# ARM_board.net
KiCad netlist of a schematic drawn in EAGLE
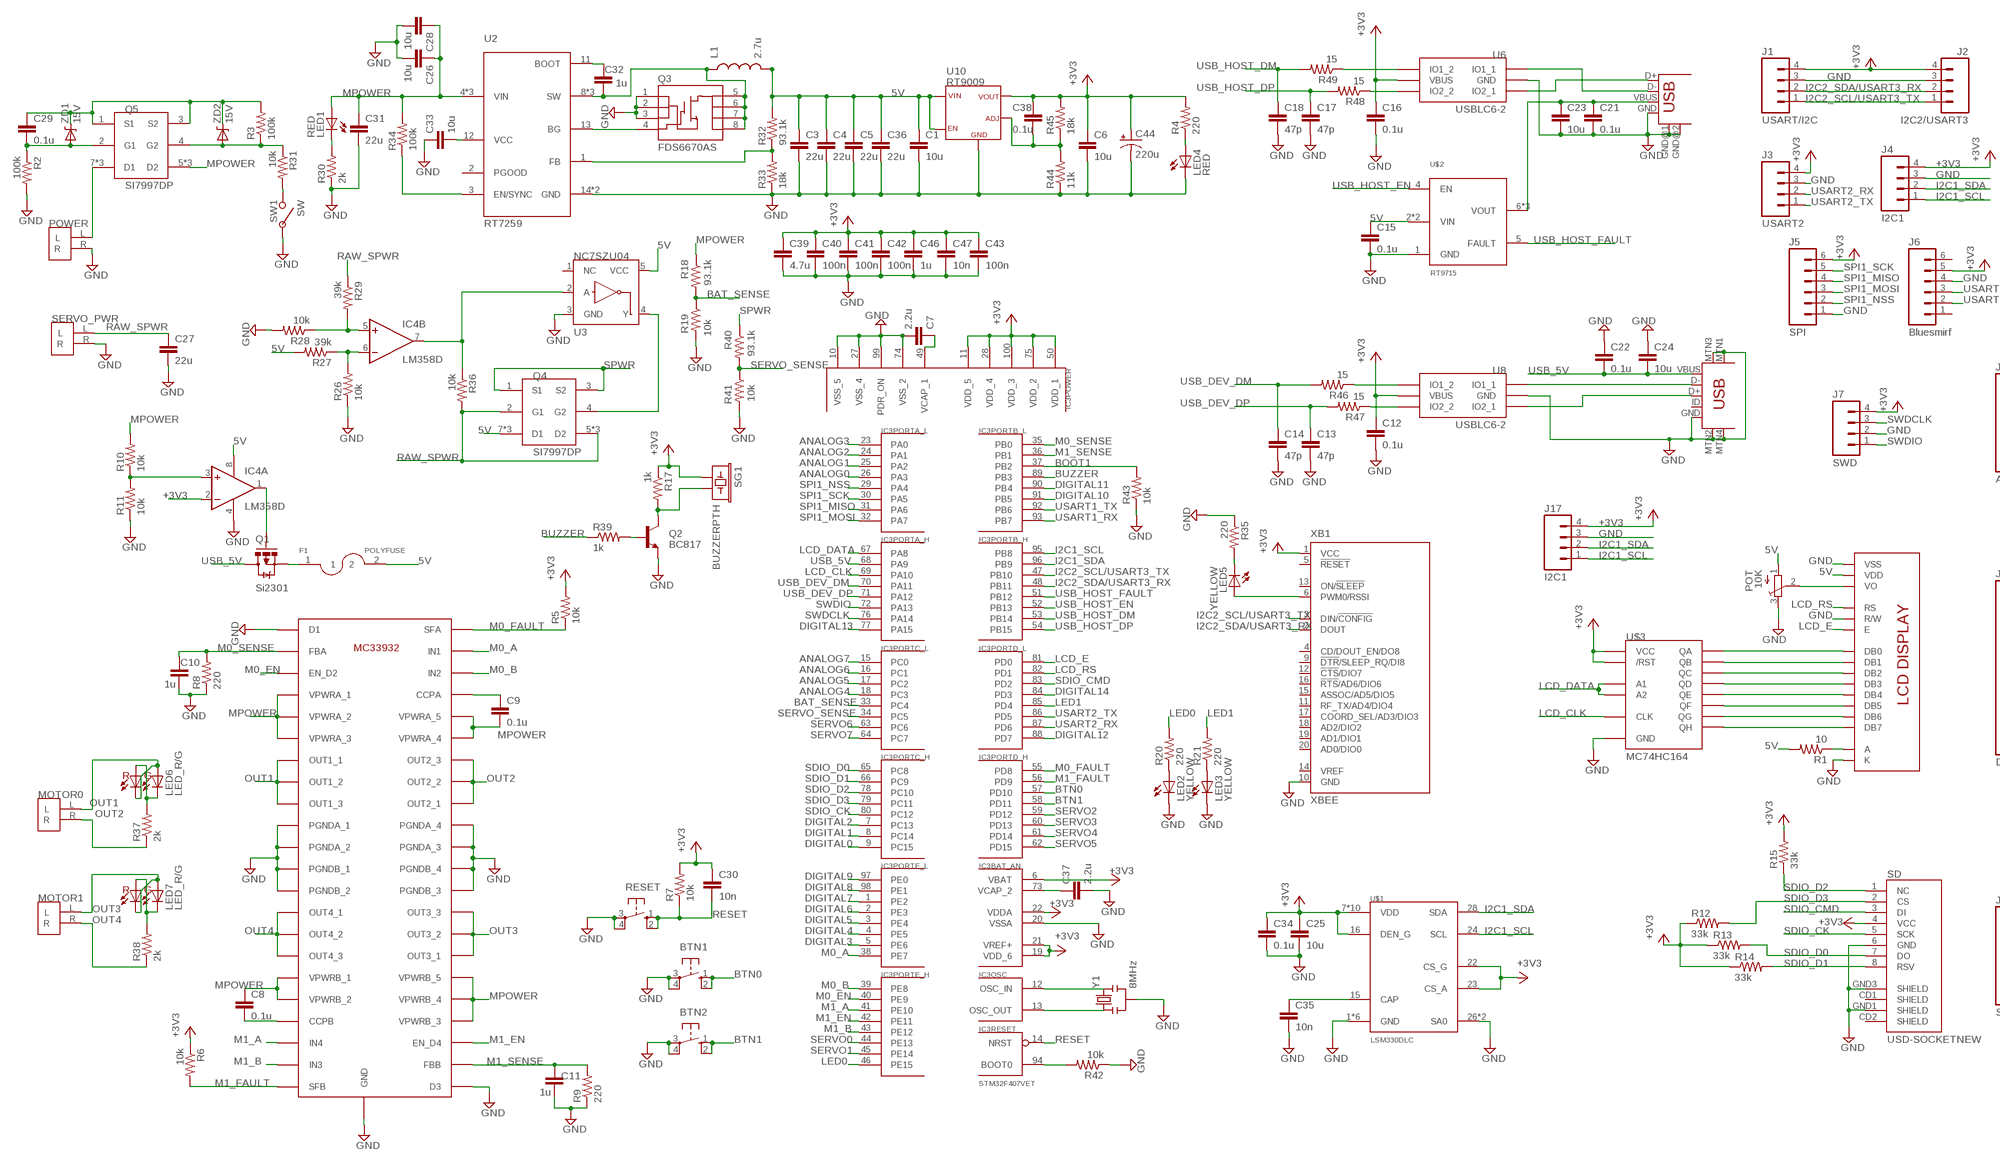
[diagram p0: schematic, sheet 1, part 1 of 2]
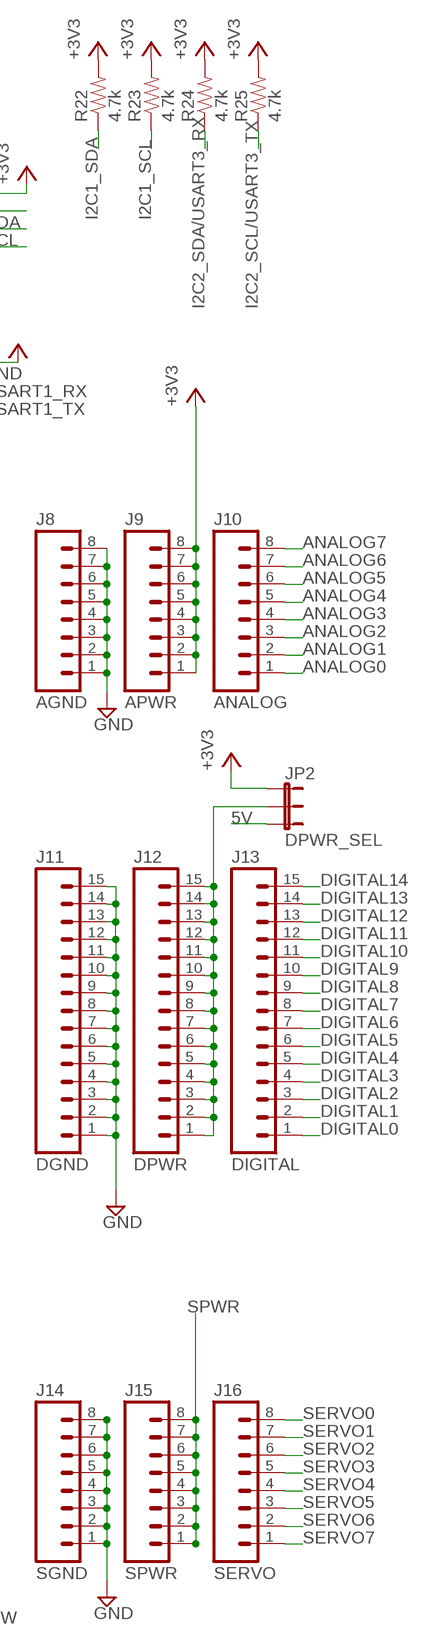
[diagram p1: schematic, sheet 1, part 2 of 2]

(export (version "E")
  (design (tool "Eeschema 10.0.6"))
  (components
    (comp (ref "BTN1")
      (value "10-XX")
      (footprint "eagle-import:B3F-10XX")
      (fields (field (name "MPN") "B3F-1000"))
      (libsource (lib "eagle-import") (part "10-XX"))
    )
    (comp (ref "BTN2")
      (value "10-XX")
      (footprint "eagle-import:B3F-10XX")
      (fields (field (name "MPN") "B3F-1000"))
      (libsource (lib "eagle-import") (part "10-XX"))
    )
    (comp (ref "C1")
      (value "10u")
      (footprint "eagle-import:0805")
      (libsource (lib "eagle-import") (part "CAP0805"))
    )
    (comp (ref "C3")
      (value "22u")
      (footprint "eagle-import:0805")
      (libsource (lib "eagle-import") (part "CAP0805"))
    )
    (comp (ref "C4")
      (value "22u")
      (footprint "eagle-import:0805")
      (libsource (lib "eagle-import") (part "CAP0805"))
    )
    (comp (ref "C5")
      (value "22u")
      (footprint "eagle-import:0805")
      (libsource (lib "eagle-import") (part "CAP0805"))
    )
    (comp (ref "C6")
      (value "10u")
      (footprint "eagle-import:0805")
      (libsource (lib "eagle-import") (part "CAP0805"))
    )
    (comp (ref "C7")
      (value "2.2u")
      (footprint "eagle-import:0603-CAP")
      (libsource (lib "eagle-import") (part "CAP0603-CAP"))
    )
    (comp (ref "C8")
      (value "0.1u")
      (footprint "eagle-import:0603-CAP")
      (libsource (lib "eagle-import") (part "CAP0603-CAP"))
    )
    (comp (ref "C9")
      (value "0.1u")
      (footprint "eagle-import:0603-CAP")
      (libsource (lib "eagle-import") (part "CAP0603-CAP"))
    )
    (comp (ref "C10")
      (value "1u")
      (footprint "eagle-import:0603-CAP")
      (libsource (lib "eagle-import") (part "CAP0603-CAP"))
    )
    (comp (ref "C11")
      (value "1u")
      (footprint "eagle-import:0603-CAP")
      (libsource (lib "eagle-import") (part "CAP0603-CAP"))
    )
    (comp (ref "C12")
      (value "0.1u")
      (footprint "eagle-import:0603-CAP")
      (libsource (lib "eagle-import") (part "CAP0603-CAP"))
    )
    (comp (ref "C13")
      (value "47p")
      (footprint "eagle-import:0603-CAP")
      (libsource (lib "eagle-import") (part "CAP0603-CAP"))
    )
    (comp (ref "C14")
      (value "47p")
      (footprint "eagle-import:0603-CAP")
      (libsource (lib "eagle-import") (part "CAP0603-CAP"))
    )
    (comp (ref "C15")
      (value "0.1u")
      (footprint "eagle-import:0603-CAP")
      (libsource (lib "eagle-import") (part "CAP0603-CAP"))
    )
    (comp (ref "C16")
      (value "0.1u")
      (footprint "eagle-import:0603-CAP")
      (libsource (lib "eagle-import") (part "CAP0603-CAP"))
    )
    (comp (ref "C17")
      (value "47p")
      (footprint "eagle-import:0603-CAP")
      (libsource (lib "eagle-import") (part "CAP0603-CAP"))
    )
    (comp (ref "C18")
      (value "47p")
      (footprint "eagle-import:0603-CAP")
      (libsource (lib "eagle-import") (part "CAP0603-CAP"))
    )
    (comp (ref "C21")
      (value "0.1u")
      (footprint "eagle-import:0603-CAP")
      (libsource (lib "eagle-import") (part "CAP0603-CAP"))
    )
    (comp (ref "C22")
      (value "0.1u")
      (footprint "eagle-import:0603-CAP")
      (libsource (lib "eagle-import") (part "CAP0603-CAP"))
    )
    (comp (ref "C23")
      (value "10u")
      (footprint "eagle-import:0805")
      (libsource (lib "eagle-import") (part "CAP0805"))
    )
    (comp (ref "C24")
      (value "10u")
      (footprint "eagle-import:0805")
      (libsource (lib "eagle-import") (part "CAP0805"))
    )
    (comp (ref "C25")
      (value "10u")
      (footprint "eagle-import:0603-CAP")
      (libsource (lib "eagle-import") (part "CAP0603-CAP"))
    )
    (comp (ref "C26")
      (value "10u")
      (footprint "eagle-import:1206")
      (libsource (lib "eagle-import") (part "CAP1206"))
    )
    (comp (ref "C27")
      (value "22u")
      (footprint "eagle-import:1206")
      (libsource (lib "eagle-import") (part "CAP1206"))
    )
    (comp (ref "C28")
      (value "10u")
      (footprint "eagle-import:1206")
      (libsource (lib "eagle-import") (part "CAP1206"))
    )
    (comp (ref "C29")
      (value "0.1u")
      (footprint "eagle-import:0603-CAP")
      (libsource (lib "eagle-import") (part "CAP0603-CAP"))
    )
    (comp (ref "C30")
      (value "10n")
      (footprint "eagle-import:0603-CAP")
      (libsource (lib "eagle-import") (part "CAP0603-CAP"))
    )
    (comp (ref "C31")
      (value "22u")
      (footprint "eagle-import:1206")
      (libsource (lib "eagle-import") (part "CAP1206"))
    )
    (comp (ref "C32")
      (value "1u")
      (footprint "eagle-import:0603-CAP")
      (libsource (lib "eagle-import") (part "CAP0603-CAP"))
    )
    (comp (ref "C33")
      (value "10u")
      (footprint "eagle-import:0805")
      (libsource (lib "eagle-import") (part "CAP0805"))
    )
    (comp (ref "C34")
      (value "0.1u")
      (footprint "eagle-import:0603-CAP")
      (libsource (lib "eagle-import") (part "CAP0603-CAP"))
    )
    (comp (ref "C35")
      (value "10n")
      (footprint "eagle-import:0603-CAP")
      (libsource (lib "eagle-import") (part "CAP0603-CAP"))
    )
    (comp (ref "C36")
      (value "22u")
      (footprint "eagle-import:0805")
      (libsource (lib "eagle-import") (part "CAP0805"))
    )
    (comp (ref "C37")
      (value "2.2u")
      (footprint "eagle-import:0603-CAP")
      (libsource (lib "eagle-import") (part "CAP0603-CAP"))
    )
    (comp (ref "C38")
      (value "0.1u")
      (footprint "eagle-import:0603-CAP")
      (libsource (lib "eagle-import") (part "CAP0603-CAP"))
    )
    (comp (ref "C39")
      (value "4.7u")
      (footprint "eagle-import:0603-CAP")
      (libsource (lib "eagle-import") (part "CAP0603-CAP"))
    )
    (comp (ref "C40")
      (value "100n")
      (footprint "eagle-import:0603-CAP")
      (libsource (lib "eagle-import") (part "CAP0603-CAP"))
    )
    (comp (ref "C41")
      (value "100n")
      (footprint "eagle-import:0603-CAP")
      (libsource (lib "eagle-import") (part "CAP0603-CAP"))
    )
    (comp (ref "C42")
      (value "100n")
      (footprint "eagle-import:0603-CAP")
      (libsource (lib "eagle-import") (part "CAP0603-CAP"))
    )
    (comp (ref "C43")
      (value "100n")
      (footprint "eagle-import:0603-CAP")
      (libsource (lib "eagle-import") (part "CAP0603-CAP"))
    )
    (comp (ref "C44")
      (value "220u")
      (footprint "eagle-import:PANASONIC_D")
      (libsource (lib "eagle-import") (part "CAP_POLD"))
    )
    (comp (ref "C46")
      (value "1u")
      (footprint "eagle-import:0603-CAP")
      (libsource (lib "eagle-import") (part "CAP0603-CAP"))
    )
    (comp (ref "C47")
      (value "10n")
      (footprint "eagle-import:0603-CAP")
      (libsource (lib "eagle-import") (part "CAP0603-CAP"))
    )
    (comp (ref "F1")
      (value "POLYFUSE")
      (footprint "eagle-import:1206")
      (libsource (lib "eagle-import") (part "POLYFUSE"))
    )
    (comp (ref "IC3")
      (value "STM32F407VET")
      (footprint "eagle-import:TQFP100")
      (libsource (lib "eagle-import") (part "STM32F407VET"))
    )
    (comp (ref "IC4")
      (value "LM358D")
      (footprint "eagle-import:SO08")
      (libsource (lib "eagle-import") (part "LM358D"))
    )
    (comp (ref "J1")
      (value "USART/I2C")
      (footprint "eagle-import:1X04")
      (libsource (lib "eagle-import") (part "M04PTH"))
    )
    (comp (ref "J2")
      (value "I2C2/USART3")
      (footprint "eagle-import:1X04")
      (libsource (lib "eagle-import") (part "M04PTH"))
    )
    (comp (ref "J3")
      (value "USART2")
      (footprint "eagle-import:1X04")
      (libsource (lib "eagle-import") (part "M04PTH"))
    )
    (comp (ref "J4")
      (value "I2C1")
      (footprint "eagle-import:1X04")
      (libsource (lib "eagle-import") (part "M04PTH"))
    )
    (comp (ref "J5")
      (value "SPI")
      (footprint "eagle-import:1X06")
      (libsource (lib "eagle-import") (part "M06SIP"))
    )
    (comp (ref "J6")
      (value "Bluesmirf")
      (footprint "eagle-import:1X06")
      (libsource (lib "eagle-import") (part "M06SIP"))
    )
    (comp (ref "J7")
      (value "SWD")
      (footprint "eagle-import:1X04")
      (libsource (lib "eagle-import") (part "M04PTH"))
    )
    (comp (ref "J8")
      (value "AGND")
      (footprint "eagle-import:1X08")
      (libsource (lib "eagle-import") (part "M081X08"))
    )
    (comp (ref "J9")
      (value "APWR")
      (footprint "eagle-import:1X08")
      (libsource (lib "eagle-import") (part "M081X08"))
    )
    (comp (ref "J10")
      (value "ANALOG")
      (footprint "eagle-import:1X08")
      (libsource (lib "eagle-import") (part "M081X08"))
    )
    (comp (ref "J11")
      (value "DGND")
      (footprint "eagle-import:1X15")
      (libsource (lib "eagle-import") (part "M15"))
    )
    (comp (ref "J12")
      (value "DPWR")
      (footprint "eagle-import:1X15")
      (libsource (lib "eagle-import") (part "M15"))
    )
    (comp (ref "J13")
      (value "DIGITAL")
      (footprint "eagle-import:1X15")
      (libsource (lib "eagle-import") (part "M15"))
    )
    (comp (ref "J14")
      (value "SGND")
      (footprint "eagle-import:1X08")
      (libsource (lib "eagle-import") (part "M081X08"))
    )
    (comp (ref "J15")
      (value "SPWR")
      (footprint "eagle-import:1X08")
      (libsource (lib "eagle-import") (part "M081X08"))
    )
    (comp (ref "J16")
      (value "SERVO")
      (footprint "eagle-import:1X08")
      (libsource (lib "eagle-import") (part "M081X08"))
    )
    (comp (ref "J17")
      (value "I2C1")
      (footprint "eagle-import:1X04")
      (libsource (lib "eagle-import") (part "M04PTH"))
    )
    (comp (ref "JP2")
      (value "DPWR_SEL")
      (footprint "eagle-import:1X03")
      (libsource (lib "eagle-import") (part "JUMPER-3PTH"))
    )
    (comp (ref "L1")
      (value "2.7u")
      (footprint "eagle-import:INDUCTOR")
      (libsource (lib "eagle-import") (part "INDUCTOR"))
    )
    (comp (ref "LCD")
      (value "LCD_DISPLAY")
      (footprint "eagle-import:LCD")
      (libsource (lib "eagle-import") (part "LCD_DISPLAY"))
    )
    (comp (ref "LED1")
      (value "RED")
      (footprint "eagle-import:CHIP-LED0603")
      (libsource (lib "eagle-import") (part "LEDCHIP-LED0603"))
    )
    (comp (ref "LED2")
      (value "YELLOW")
      (footprint "eagle-import:CHIP-LED0603")
      (libsource (lib "eagle-import") (part "LEDCHIP-LED0603"))
    )
    (comp (ref "LED3")
      (value "YELLOW")
      (footprint "eagle-import:CHIP-LED0603")
      (libsource (lib "eagle-import") (part "LEDCHIP-LED0603"))
    )
    (comp (ref "LED4")
      (value "RED")
      (footprint "eagle-import:CHIP-LED0603")
      (libsource (lib "eagle-import") (part "LEDCHIP-LED0603"))
    )
    (comp (ref "LED5")
      (value "YELLOW")
      (footprint "eagle-import:CHIP-LED0603")
      (libsource (lib "eagle-import") (part "LEDCHIP-LED0603"))
    )
    (comp (ref "LED6")
      (value "LED_R/G")
      (footprint "eagle-import:LED-0606")
      (libsource (lib "eagle-import") (part "LED_BICOLOR"))
    )
    (comp (ref "LED7")
      (value "LED_R/G")
      (footprint "eagle-import:LED-0606")
      (libsource (lib "eagle-import") (part "LED_BICOLOR"))
    )
    (comp (ref "MOTOR0")
      (value "2POS_TERMINAL")
      (footprint "eagle-import:2POS_TERMINAL")
      (libsource (lib "eagle-import") (part "2POS_TERMINAL"))
    )
    (comp (ref "MOTOR1")
      (value "2POS_TERMINAL")
      (footprint "eagle-import:2POS_TERMINAL")
      (libsource (lib "eagle-import") (part "2POS_TERMINAL"))
    )
    (comp (ref "POT")
      (value "10K")
      (footprint "eagle-import:POT")
      (libsource (lib "eagle-import") (part "POT"))
    )
    (comp (ref "POWER")
      (value "2POS_TERMINAL")
      (footprint "eagle-import:2POS_TERMINAL")
      (libsource (lib "eagle-import") (part "2POS_TERMINAL"))
    )
    (comp (ref "Q1")
      (value "Si2301")
      (footprint "eagle-import:SOT23-3")
      (libsource (lib "eagle-import") (part "MOSFET-PCHANNELSMD"))
    )
    (comp (ref "Q2")
      (value "BC817")
      (footprint "eagle-import:SOT23-3")
      (libsource (lib "eagle-import") (part "TRANSISTOR_NPNSOT23-3"))
    )
    (comp (ref "Q3")
      (value "FDS6670AS")
      (footprint "eagle-import:SO08")
      (libsource (lib "eagle-import") (part "MOSFET-NCHANNEL-SOIC8"))
    )
    (comp (ref "Q4")
      (value "SI7997DP")
      (footprint "eagle-import:POWERPAK")
      (libsource (lib "eagle-import") (part "SI7997DP"))
    )
    (comp (ref "Q5")
      (value "SI7997DP")
      (footprint "eagle-import:POWERPAK")
      (libsource (lib "eagle-import") (part "SI7997DP"))
    )
    (comp (ref "R1")
      (value "10")
      (footprint "eagle-import:0603-RES")
      (libsource (lib "eagle-import") (part "RESISTOR0603-RES"))
    )
    (comp (ref "R2")
      (value "100k")
      (footprint "eagle-import:0603-RES")
      (libsource (lib "eagle-import") (part "RESISTOR0603-RES"))
    )
    (comp (ref "R3")
      (value "100k")
      (footprint "eagle-import:0603-RES")
      (libsource (lib "eagle-import") (part "RESISTOR0603-RES"))
    )
    (comp (ref "R4")
      (value "220")
      (footprint "eagle-import:0603-RES")
      (libsource (lib "eagle-import") (part "RESISTOR0603-RES"))
    )
    (comp (ref "R5")
      (value "10k")
      (footprint "eagle-import:0603-RES")
      (libsource (lib "eagle-import") (part "RESISTOR0603-RES"))
    )
    (comp (ref "R6")
      (value "10k")
      (footprint "eagle-import:0603-RES")
      (libsource (lib "eagle-import") (part "RESISTOR0603-RES"))
    )
    (comp (ref "R7")
      (value "10k")
      (footprint "eagle-import:0603-RES")
      (libsource (lib "eagle-import") (part "RESISTOR0603-RES"))
    )
    (comp (ref "R8")
      (value "220")
      (footprint "eagle-import:0603-RES")
      (libsource (lib "eagle-import") (part "RESISTOR0603-RES"))
    )
    (comp (ref "R9")
      (value "220")
      (footprint "eagle-import:0603-RES")
      (libsource (lib "eagle-import") (part "RESISTOR0603-RES"))
    )
    (comp (ref "R10")
      (value "10k")
      (footprint "eagle-import:0603-RES")
      (libsource (lib "eagle-import") (part "RESISTOR0603-RES"))
    )
    (comp (ref "R11")
      (value "10k")
      (footprint "eagle-import:0603-RES")
      (libsource (lib "eagle-import") (part "RESISTOR0603-RES"))
    )
    (comp (ref "R12")
      (value "33k")
      (footprint "eagle-import:0603-RES")
      (libsource (lib "eagle-import") (part "RESISTOR0603-RES"))
    )
    (comp (ref "R13")
      (value "33k")
      (footprint "eagle-import:0603-RES")
      (libsource (lib "eagle-import") (part "RESISTOR0603-RES"))
    )
    (comp (ref "R14")
      (value "33k")
      (footprint "eagle-import:0603-RES")
      (libsource (lib "eagle-import") (part "RESISTOR0603-RES"))
    )
    (comp (ref "R15")
      (value "33k")
      (footprint "eagle-import:0603-RES")
      (libsource (lib "eagle-import") (part "RESISTOR0603-RES"))
    )
    (comp (ref "R17")
      (value "1k")
      (footprint "eagle-import:0603-RES")
      (libsource (lib "eagle-import") (part "RESISTOR0603-RES"))
    )
    (comp (ref "R18")
      (value "93.1k")
      (footprint "eagle-import:0603-RES")
      (libsource (lib "eagle-import") (part "RESISTOR0603-RES"))
    )
    (comp (ref "R19")
      (value "10k")
      (footprint "eagle-import:0603-RES")
      (libsource (lib "eagle-import") (part "RESISTOR0603-RES"))
    )
    (comp (ref "R20")
      (value "220")
      (footprint "eagle-import:0603-RES")
      (libsource (lib "eagle-import") (part "RESISTOR0603-RES"))
    )
    (comp (ref "R21")
      (value "220")
      (footprint "eagle-import:0603-RES")
      (libsource (lib "eagle-import") (part "RESISTOR0603-RES"))
    )
    (comp (ref "R22")
      (value "4.7k")
      (footprint "eagle-import:0603-RES")
      (libsource (lib "eagle-import") (part "RESISTOR0603-RES"))
    )
    (comp (ref "R23")
      (value "4.7k")
      (footprint "eagle-import:0603-RES")
      (libsource (lib "eagle-import") (part "RESISTOR0603-RES"))
    )
    (comp (ref "R24")
      (value "4.7k")
      (footprint "eagle-import:0603-RES")
      (libsource (lib "eagle-import") (part "RESISTOR0603-RES"))
    )
    (comp (ref "R25")
      (value "4.7k")
      (footprint "eagle-import:0603-RES")
      (libsource (lib "eagle-import") (part "RESISTOR0603-RES"))
    )
    (comp (ref "R26")
      (value "10k")
      (footprint "eagle-import:0603-RES")
      (libsource (lib "eagle-import") (part "RESISTOR0603-RES"))
    )
    (comp (ref "R27")
      (value "39k")
      (footprint "eagle-import:0603-RES")
      (libsource (lib "eagle-import") (part "RESISTOR0603-RES"))
    )
    (comp (ref "R28")
      (value "10k")
      (footprint "eagle-import:0603-RES")
      (libsource (lib "eagle-import") (part "RESISTOR0603-RES"))
    )
    (comp (ref "R29")
      (value "39k")
      (footprint "eagle-import:0603-RES")
      (libsource (lib "eagle-import") (part "RESISTOR0603-RES"))
    )
    (comp (ref "R30")
      (value "2k")
      (footprint "eagle-import:0603-RES")
      (libsource (lib "eagle-import") (part "RESISTOR0603-RES"))
    )
    (comp (ref "R31")
      (value "10k")
      (footprint "eagle-import:0603-RES")
      (libsource (lib "eagle-import") (part "RESISTOR0603-RES"))
    )
    (comp (ref "R32")
      (value "93.1k")
      (footprint "eagle-import:0603-RES")
      (libsource (lib "eagle-import") (part "RESISTOR0603-RES"))
    )
    (comp (ref "R33")
      (value "18k")
      (footprint "eagle-import:0603-RES")
      (libsource (lib "eagle-import") (part "RESISTOR0603-RES"))
    )
    (comp (ref "R34")
      (value "100k")
      (footprint "eagle-import:0603-RES")
      (libsource (lib "eagle-import") (part "RESISTOR0603-RES"))
    )
    (comp (ref "R35")
      (value "220")
      (footprint "eagle-import:0603-RES")
      (libsource (lib "eagle-import") (part "RESISTOR0603-RES"))
    )
    (comp (ref "R36")
      (value "10k")
      (footprint "eagle-import:0603-RES")
      (libsource (lib "eagle-import") (part "RESISTOR0603-RES"))
    )
    (comp (ref "R37")
      (value "2k")
      (footprint "eagle-import:0603-RES")
      (libsource (lib "eagle-import") (part "RESISTOR0603-RES"))
    )
    (comp (ref "R38")
      (value "2k")
      (footprint "eagle-import:0603-RES")
      (libsource (lib "eagle-import") (part "RESISTOR0603-RES"))
    )
    (comp (ref "R39")
      (value "1k")
      (footprint "eagle-import:0603-RES")
      (libsource (lib "eagle-import") (part "RESISTOR0603-RES"))
    )
    (comp (ref "R40")
      (value "93.1k")
      (footprint "eagle-import:0603-RES")
      (libsource (lib "eagle-import") (part "RESISTOR0603-RES"))
    )
    (comp (ref "R41")
      (value "10k")
      (footprint "eagle-import:0603-RES")
      (libsource (lib "eagle-import") (part "RESISTOR0603-RES"))
    )
    (comp (ref "R42")
      (value "10k")
      (footprint "eagle-import:0603-RES")
      (libsource (lib "eagle-import") (part "RESISTOR0603-RES"))
    )
    (comp (ref "R43")
      (value "10k")
      (footprint "eagle-import:0603-RES")
      (libsource (lib "eagle-import") (part "RESISTOR0603-RES"))
    )
    (comp (ref "R44")
      (value "11k")
      (footprint "eagle-import:0603-RES")
      (libsource (lib "eagle-import") (part "RESISTOR0603-RES"))
    )
    (comp (ref "R45")
      (value "18k")
      (footprint "eagle-import:0603-RES")
      (libsource (lib "eagle-import") (part "RESISTOR0603-RES"))
    )
    (comp (ref "R46")
      (value "15")
      (footprint "eagle-import:0603-RES")
      (libsource (lib "eagle-import") (part "RESISTOR0603-RES"))
    )
    (comp (ref "R47")
      (value "15")
      (footprint "eagle-import:0603-RES")
      (libsource (lib "eagle-import") (part "RESISTOR0603-RES"))
    )
    (comp (ref "R48")
      (value "15")
      (footprint "eagle-import:0603-RES")
      (libsource (lib "eagle-import") (part "RESISTOR0603-RES"))
    )
    (comp (ref "R49")
      (value "15")
      (footprint "eagle-import:0603-RES")
      (libsource (lib "eagle-import") (part "RESISTOR0603-RES"))
    )
    (comp (ref "RESET")
      (value "10-XX")
      (footprint "eagle-import:B3F-10XX")
      (fields (field (name "MPN") "B3F-1000"))
      (libsource (lib "eagle-import") (part "10-XX"))
    )
    (comp (ref "SD")
      (value "USD-SOCKETNEW")
      (footprint "eagle-import:MICRO-SD-SOCKET-PP")
      (libsource (lib "eagle-import") (part "USD-SOCKETNEW"))
    )
    (comp (ref "SERVO_PWR")
      (value "2POS_TERMINAL")
      (footprint "eagle-import:2POS_TERMINAL")
      (libsource (lib "eagle-import") (part "2POS_TERMINAL"))
    )
    (comp (ref "SG1")
      (value "BUZZERPTH")
      (footprint "eagle-import:BUZZER-12MM")
      (libsource (lib "eagle-import") (part "BUZZERPTH"))
    )
    (comp (ref "SW1") (value "SW") (footprint "eagle-import:SW") (libsource (lib "eagle-import") (part "SW")))
    (comp (ref "U$1")
      (value "LSM330DLC")
      (footprint "eagle-import:LGA-28")
      (libsource (lib "eagle-import") (part "LSM330DLC"))
    )
    (comp (ref "U$2")
      (value "RT9715")
      (footprint "eagle-import:8-SOIC")
      (libsource (lib "eagle-import") (part "RT9715"))
    )
    (comp (ref "U$3")
      (value "MC74HC164")
      (footprint "eagle-import:TSSOP-14")
      (libsource (lib "eagle-import") (part "MC74HC164"))
    )
    (comp (ref "U1")
      (value "MC33932")
      (footprint "eagle-import:HSOP44")
      (libsource (lib "eagle-import") (part "MC33932"))
    )
    (comp (ref "U2")
      (value "RT7259")
      (footprint "eagle-import:WDFN-14L")
      (libsource (lib "eagle-import") (part "SWITCHING_REG"))
    )
    (comp (ref "U3")
      (value "NC7SZU04")
      (footprint "eagle-import:SC70")
      (libsource (lib "eagle-import") (part "INVERTER{dblquote}{dblquote}"))
    )
    (comp (ref "U6")
      (value "USBLC6-2")
      (footprint "eagle-import:SOT23-6L")
      (libsource (lib "eagle-import") (part "USBLC6-2"))
    )
    (comp (ref "U8")
      (value "USBLC6-2")
      (footprint "eagle-import:SOT23-6L")
      (libsource (lib "eagle-import") (part "USBLC6-2"))
    )
    (comp (ref "U10")
      (value "RT9009")
      (footprint "eagle-import:D2PAK-5")
      (libsource (lib "eagle-import") (part "RT9009"))
    )
    (comp (ref "USB1")
      (value "USB-A-S")
      (footprint "eagle-import:USB-A-S")
      (libsource (lib "eagle-import") (part "USB-A-S"))
    )
    (comp (ref "USB2")
      (value "USB-MINIB-5PIN")
      (footprint "eagle-import:USB-MINIB")
      (libsource (lib "eagle-import") (part "USB-MINIB-5PIN"))
    )
    (comp (ref "XB1")
      (value "XBEE")
      (footprint "eagle-import:XBEE")
      (fields
        (field (name "MPN") "XBP24-Z7UIT-004")
        (field (name "MPN_1") "XBP24-Z7UIT-004")
        (field (name "OC_FARNELL") "1751799")
        (field (name "OC_NEWARK") "34R5507")
      )
      (libsource (lib "eagle-import") (part "XBEE"))
    )
    (comp (ref "Y1")
      (value "8MHz")
      (footprint "eagle-import:RESONATOR")
      (libsource (lib "eagle-import") (part "RESONATOR"))
    )
    (comp (ref "ZD1")
      (value "15V")
      (footprint "eagle-import:0603")
      (libsource (lib "eagle-import") (part "ZENER"))
    )
    (comp (ref "ZD2")
      (value "15V")
      (footprint "eagle-import:0603")
      (libsource (lib "eagle-import") (part "ZENER"))
    )
  )
  (nets
    (net (code "1") (name "+3V3") (class "Default")
      (node (ref "C12") (pin "1") (pinfunction "1_1") (pintype "passive"))
      (node (ref "C16") (pin "1") (pinfunction "1_1") (pintype "passive"))
      (node (ref "C25") (pin "1") (pinfunction "1_1") (pintype "passive"))
      (node (ref "C30") (pin "1") (pinfunction "1_1") (pintype "passive"))
      (node (ref "C34") (pin "1") (pinfunction "1_1") (pintype "passive"))
      (node (ref "C38") (pin "1") (pinfunction "1_1") (pintype "passive"))
      (node (ref "C39") (pin "1") (pinfunction "1_1") (pintype "passive"))
      (node (ref "C40") (pin "1") (pinfunction "1_1") (pintype "passive"))
      (node (ref "C41") (pin "1") (pinfunction "1_1") (pintype "passive"))
      (node (ref "C42") (pin "1") (pinfunction "1_1") (pintype "passive"))
      (node (ref "C43") (pin "1") (pinfunction "1_1") (pintype "passive"))
      (node (ref "C44") (pin "+") (pinfunction "+_+") (pintype "passive"))
      (node (ref "C46") (pin "1") (pinfunction "1_1") (pintype "passive"))
      (node (ref "C47") (pin "1") (pinfunction "1_1") (pintype "passive"))
      (node (ref "C6") (pin "1") (pinfunction "1_1") (pintype "passive"))
      (node (ref "IC3") (pin "100") (pinfunction "VDD_3_100") (pintype "power_in"))
      (node (ref "IC3") (pin "11") (pinfunction "VDD_5_11") (pintype "power_in"))
      (node (ref "IC3") (pin "19") (pinfunction "VDD_6_19") (pintype "input"))
      (node (ref "IC3") (pin "21") (pinfunction "VREF+_21") (pintype "input"))
      (node (ref "IC3") (pin "22") (pinfunction "VDDA_22") (pintype "power_in"))
      (node (ref "IC3") (pin "28") (pinfunction "VDD_4_28") (pintype "power_in"))
      (node (ref "IC3") (pin "50") (pinfunction "VDD_1_50") (pintype "power_in"))
      (node (ref "IC3") (pin "6") (pinfunction "VBAT_6") (pintype "power_in"))
      (node (ref "IC3") (pin "75") (pinfunction "VDD_2_75") (pintype "power_in"))
      (node (ref "IC4") (pin "2") (pinfunction "-IN_2") (pintype "input"))
      (node (ref "J1") (pin "4") (pinfunction "4_4") (pintype "passive"))
      (node (ref "J17") (pin "4") (pinfunction "4_4") (pintype "passive"))
      (node (ref "J2") (pin "4") (pinfunction "4_4") (pintype "passive"))
      (node (ref "J3") (pin "4") (pinfunction "4_4") (pintype "passive"))
      (node (ref "J4") (pin "4") (pinfunction "4_4") (pintype "passive"))
      (node (ref "J5") (pin "6") (pinfunction "6_6") (pintype "passive"))
      (node (ref "J6") (pin "5") (pinfunction "5_5") (pintype "passive"))
      (node (ref "J7") (pin "4") (pinfunction "4_4") (pintype "passive"))
      (node (ref "J9") (pin "1") (pinfunction "1_1") (pintype "passive"))
      (node (ref "J9") (pin "2") (pinfunction "2_2") (pintype "passive"))
      (node (ref "J9") (pin "3") (pinfunction "3_3") (pintype "passive"))
      (node (ref "J9") (pin "4") (pinfunction "4_4") (pintype "passive"))
      (node (ref "J9") (pin "5") (pinfunction "5_5") (pintype "passive"))
      (node (ref "J9") (pin "6") (pinfunction "6_6") (pintype "passive"))
      (node (ref "J9") (pin "7") (pinfunction "7_7") (pintype "passive"))
      (node (ref "J9") (pin "8") (pinfunction "8_8") (pintype "passive"))
      (node (ref "JP2") (pin "1") (pinfunction "1_1") (pintype "passive"))
      (node (ref "R12") (pin "1") (pinfunction "1_1") (pintype "passive"))
      (node (ref "R13") (pin "1") (pinfunction "1_1") (pintype "passive"))
      (node (ref "R14") (pin "1") (pinfunction "1_1") (pintype "passive"))
      (node (ref "R15") (pin "2") (pinfunction "2_2") (pintype "passive"))
      (node (ref "R17") (pin "1") (pinfunction "1_1") (pintype "passive"))
      (node (ref "R22") (pin "2") (pinfunction "2_2") (pintype "passive"))
      (node (ref "R23") (pin "2") (pinfunction "2_2") (pintype "passive"))
      (node (ref "R24") (pin "2") (pinfunction "2_2") (pintype "passive"))
      (node (ref "R25") (pin "2") (pinfunction "2_2") (pintype "passive"))
      (node (ref "R4") (pin "2") (pinfunction "2_2") (pintype "passive"))
      (node (ref "R45") (pin "2") (pinfunction "2_2") (pintype "passive"))
      (node (ref "R5") (pin "2") (pinfunction "2_2") (pintype "passive"))
      (node (ref "R6") (pin "1") (pinfunction "1_1") (pintype "passive"))
      (node (ref "R7") (pin "2") (pinfunction "2_2") (pintype "passive"))
      (node (ref "SD") (pin "4") (pinfunction "VCC_4") (pintype "bidirectional"))
      (node (ref "SG1") (pin "+") (pinfunction "1_+") (pintype "passive"))
      (node (ref "U$1") (pin "10") (pinfunction "VDD_10") (pintype "bidirectional"))
      (node (ref "U$1") (pin "11") (pinfunction "VDD_11") (pintype "bidirectional"))
      (node (ref "U$1") (pin "12") (pinfunction "VDD_12") (pintype "bidirectional"))
      (node (ref "U$1") (pin "13") (pinfunction "VDD_13") (pintype "bidirectional"))
      (node (ref "U$1") (pin "14") (pinfunction "VDD_14") (pintype "bidirectional"))
      (node (ref "U$1") (pin "16") (pinfunction "DEN_G_16") (pintype "bidirectional"))
      (node (ref "U$1") (pin "21") (pinfunction "VDD_21") (pintype "bidirectional"))
      (node (ref "U$1") (pin "22") (pinfunction "CS_G_22") (pintype "bidirectional"))
      (node (ref "U$1") (pin "23") (pinfunction "CS_A_23") (pintype "bidirectional"))
      (node (ref "U$1") (pin "25") (pinfunction "VDD_25") (pintype "bidirectional"))
      (node (ref "U$1") (pin "7") (pinfunction "VDD_7") (pintype "bidirectional"))
      (node (ref "U$1") (pin "8") (pinfunction "VDD_8") (pintype "bidirectional"))
      (node (ref "U$1") (pin "9") (pinfunction "VDD_9") (pintype "bidirectional"))
      (node (ref "U$3") (pin "14") (pinfunction "VCC_14") (pintype "bidirectional"))
      (node (ref "U$3") (pin "9") (pinfunction "/RST_9") (pintype "bidirectional"))
      (node (ref "U10") (pin "VOUT") (pinfunction "VOUT_VOUT") (pintype "bidirectional"))
      (node (ref "U10") (pin "VOUT_PAD") (pinfunction "VOUT_VOUT_PAD") (pintype "bidirectional"))
      (node (ref "U6") (pin "P$5") (pinfunction "VBUS_P$5") (pintype "bidirectional"))
      (node (ref "U8") (pin "P$5") (pinfunction "VBUS_P$5") (pintype "bidirectional"))
      (node (ref "XB1") (pin "1") (pinfunction "VCC_1") (pintype "power_in"))
    )
    (net (code "2") (name "/5V") (class "Default")
      (node (ref "C1") (pin "1") (pinfunction "1_1") (pintype "passive"))
      (node (ref "C15") (pin "1") (pinfunction "1_1") (pintype "passive"))
      (node (ref "C3") (pin "1") (pinfunction "1_1") (pintype "passive"))
      (node (ref "C36") (pin "1") (pinfunction "1_1") (pintype "passive"))
      (node (ref "C4") (pin "1") (pinfunction "1_1") (pintype "passive"))
      (node (ref "C5") (pin "1") (pinfunction "1_1") (pintype "passive"))
      (node (ref "F1") (pin "2") (pinfunction "2_2") (pintype "bidirectional"))
      (node (ref "IC4") (pin "8") (pinfunction "V+_8") (pintype "power_in"))
      (node (ref "JP2") (pin "3") (pinfunction "3_3") (pintype "passive"))
      (node (ref "L1") (pin "P$2") (pinfunction "2_P$2") (pintype "passive"))
      (node (ref "LCD") (pin "VDD") (pinfunction "VDD_VDD") (pintype "bidirectional"))
      (node (ref "POT") (pin "1") (pinfunction "A_1") (pintype "passive"))
      (node (ref "Q4") (pin "7") (pinfunction "D1_7") (pintype "bidirectional"))
      (node (ref "Q4") (pin "8") (pinfunction "D1_8") (pintype "bidirectional"))
      (node (ref "Q4") (pin "9") (pinfunction "D1_9") (pintype "bidirectional"))
      (node (ref "R1") (pin "2") (pinfunction "2_2") (pintype "passive"))
      (node (ref "R27") (pin "2") (pinfunction "2_2") (pintype "passive"))
      (node (ref "R32") (pin "2") (pinfunction "2_2") (pintype "passive"))
      (node (ref "U$2") (pin "2") (pinfunction "VIN_2") (pintype "bidirectional"))
      (node (ref "U$2") (pin "3") (pinfunction "VIN_3") (pintype "bidirectional"))
      (node (ref "U10") (pin "EN") (pinfunction "EN_EN") (pintype "bidirectional"))
      (node (ref "U10") (pin "VIN") (pinfunction "VIN_VIN") (pintype "bidirectional"))
      (node (ref "U3") (pin "5") (pinfunction "VCC_5") (pintype "bidirectional"))
    )
    (net (code "3") (name "/ANALOG0") (class "Default")
      (node (ref "IC3") (pin "26") (pinfunction "PA3_26") (pintype "bidirectional"))
      (node (ref "J10") (pin "1") (pinfunction "1_1") (pintype "passive"))
    )
    (net (code "4") (name "/ANALOG1") (class "Default")
      (node (ref "IC3") (pin "25") (pinfunction "PA2_25") (pintype "bidirectional"))
      (node (ref "J10") (pin "2") (pinfunction "2_2") (pintype "passive"))
    )
    (net (code "5") (name "/ANALOG2") (class "Default")
      (node (ref "IC3") (pin "24") (pinfunction "PA1_24") (pintype "bidirectional"))
      (node (ref "J10") (pin "3") (pinfunction "3_3") (pintype "passive"))
    )
    (net (code "6") (name "/ANALOG3") (class "Default")
      (node (ref "IC3") (pin "23") (pinfunction "PA0_23") (pintype "bidirectional"))
      (node (ref "J10") (pin "4") (pinfunction "4_4") (pintype "passive"))
    )
    (net (code "7") (name "/ANALOG4") (class "Default")
      (node (ref "IC3") (pin "18") (pinfunction "PC3_18") (pintype "bidirectional"))
      (node (ref "J10") (pin "5") (pinfunction "5_5") (pintype "passive"))
    )
    (net (code "8") (name "/ANALOG5") (class "Default")
      (node (ref "IC3") (pin "17") (pinfunction "PC2_17") (pintype "bidirectional"))
      (node (ref "J10") (pin "6") (pinfunction "6_6") (pintype "passive"))
    )
    (net (code "9") (name "/ANALOG6") (class "Default")
      (node (ref "IC3") (pin "16") (pinfunction "PC1_16") (pintype "bidirectional"))
      (node (ref "J10") (pin "7") (pinfunction "7_7") (pintype "passive"))
    )
    (net (code "10") (name "/ANALOG7") (class "Default")
      (node (ref "IC3") (pin "15") (pinfunction "PC0_15") (pintype "bidirectional"))
      (node (ref "J10") (pin "8") (pinfunction "8_8") (pintype "passive"))
    )
    (net (code "11") (name "/BAT_SENSE") (class "Default")
      (node (ref "IC3") (pin "33") (pinfunction "PC4_33") (pintype "bidirectional"))
      (node (ref "R18") (pin "2") (pinfunction "2_2") (pintype "passive"))
      (node (ref "R19") (pin "1") (pinfunction "1_1") (pintype "passive"))
    )
    (net (code "12") (name "/BOOT1") (class "Default")
      (node (ref "IC3") (pin "37") (pinfunction "PB2_37") (pintype "bidirectional"))
      (node (ref "R43") (pin "2") (pinfunction "2_2") (pintype "passive"))
    )
    (net (code "13") (name "/BTN0") (class "Default")
      (node (ref "BTN1") (pin "1") (pinfunction "S_1") (pintype "passive"))
      (node (ref "BTN1") (pin "2") (pinfunction "S1_2") (pintype "passive"))
      (node (ref "IC3") (pin "57") (pinfunction "PD10_57") (pintype "bidirectional"))
    )
    (net (code "14") (name "/BTN1") (class "Default")
      (node (ref "BTN2") (pin "1") (pinfunction "S_1") (pintype "passive"))
      (node (ref "BTN2") (pin "2") (pinfunction "S1_2") (pintype "passive"))
      (node (ref "IC3") (pin "58") (pinfunction "PD11_58") (pintype "bidirectional"))
    )
    (net (code "15") (name "/BUZZER") (class "Default")
      (node (ref "IC3") (pin "89") (pinfunction "PB3_89") (pintype "bidirectional"))
      (node (ref "R39") (pin "1") (pinfunction "1_1") (pintype "passive"))
    )
    (net (code "16") (name "/DIGITAL0") (class "Default")
      (node (ref "IC3") (pin "9") (pinfunction "PC15_9") (pintype "bidirectional"))
      (node (ref "J13") (pin "1") (pinfunction "1_1") (pintype "passive"))
    )
    (net (code "17") (name "/DIGITAL1") (class "Default")
      (node (ref "IC3") (pin "8") (pinfunction "PC14_8") (pintype "bidirectional"))
      (node (ref "J13") (pin "2") (pinfunction "2_2") (pintype "passive"))
    )
    (net (code "18") (name "/DIGITAL2") (class "Default")
      (node (ref "IC3") (pin "7") (pinfunction "PC13_7") (pintype "bidirectional"))
      (node (ref "J13") (pin "3") (pinfunction "3_3") (pintype "passive"))
    )
    (net (code "19") (name "/DIGITAL3") (class "Default")
      (node (ref "IC3") (pin "5") (pinfunction "PE6_5") (pintype "bidirectional"))
      (node (ref "J13") (pin "4") (pinfunction "4_4") (pintype "passive"))
    )
    (net (code "20") (name "/DIGITAL4") (class "Default")
      (node (ref "IC3") (pin "4") (pinfunction "PE5_4") (pintype "bidirectional"))
      (node (ref "J13") (pin "5") (pinfunction "5_5") (pintype "passive"))
    )
    (net (code "21") (name "/DIGITAL5") (class "Default")
      (node (ref "IC3") (pin "3") (pinfunction "PE4_3") (pintype "bidirectional"))
      (node (ref "J13") (pin "6") (pinfunction "6_6") (pintype "passive"))
    )
    (net (code "22") (name "/DIGITAL6") (class "Default")
      (node (ref "IC3") (pin "2") (pinfunction "PE3_2") (pintype "bidirectional"))
      (node (ref "J13") (pin "7") (pinfunction "7_7") (pintype "passive"))
    )
    (net (code "23") (name "/DIGITAL7") (class "Default")
      (node (ref "IC3") (pin "1") (pinfunction "PE2_1") (pintype "bidirectional"))
      (node (ref "J13") (pin "8") (pinfunction "8_8") (pintype "passive"))
    )
    (net (code "24") (name "/DIGITAL8") (class "Default")
      (node (ref "IC3") (pin "98") (pinfunction "PE1_98") (pintype "bidirectional"))
      (node (ref "J13") (pin "9") (pinfunction "9_9") (pintype "passive"))
    )
    (net (code "25") (name "/DIGITAL9") (class "Default")
      (node (ref "IC3") (pin "97") (pinfunction "PE0_97") (pintype "bidirectional"))
      (node (ref "J13") (pin "10") (pinfunction "10_10") (pintype "passive"))
    )
    (net (code "26") (name "/DIGITAL10") (class "Default")
      (node (ref "IC3") (pin "91") (pinfunction "PB5_91") (pintype "bidirectional"))
      (node (ref "J13") (pin "11") (pinfunction "11_11") (pintype "passive"))
    )
    (net (code "27") (name "/DIGITAL11") (class "Default")
      (node (ref "IC3") (pin "90") (pinfunction "PB4_90") (pintype "bidirectional"))
      (node (ref "J13") (pin "12") (pinfunction "12_12") (pintype "passive"))
    )
    (net (code "28") (name "/DIGITAL12") (class "Default")
      (node (ref "IC3") (pin "88") (pinfunction "PD7_88") (pintype "bidirectional"))
      (node (ref "J13") (pin "13") (pinfunction "13_13") (pintype "passive"))
    )
    (net (code "29") (name "/DIGITAL13") (class "Default")
      (node (ref "IC3") (pin "77") (pinfunction "PA15_77") (pintype "bidirectional"))
      (node (ref "J13") (pin "14") (pinfunction "14_14") (pintype "passive"))
    )
    (net (code "30") (name "/DIGITAL14") (class "Default")
      (node (ref "IC3") (pin "84") (pinfunction "PD3_84") (pintype "bidirectional"))
      (node (ref "J13") (pin "15") (pinfunction "15_15") (pintype "passive"))
    )
    (net (code "31") (name "/I2C1_SCL") (class "Default")
      (node (ref "IC3") (pin "95") (pinfunction "PB8_95") (pintype "bidirectional"))
      (node (ref "J17") (pin "1") (pinfunction "1_1") (pintype "passive"))
      (node (ref "J4") (pin "1") (pinfunction "1_1") (pintype "passive"))
      (node (ref "R23") (pin "1") (pinfunction "1_1") (pintype "passive"))
      (node (ref "U$1") (pin "24") (pinfunction "SCL_24") (pintype "bidirectional"))
    )
    (net (code "32") (name "/I2C1_SDA") (class "Default")
      (node (ref "IC3") (pin "96") (pinfunction "PB9_96") (pintype "bidirectional"))
      (node (ref "J17") (pin "2") (pinfunction "2_2") (pintype "passive"))
      (node (ref "J4") (pin "2") (pinfunction "2_2") (pintype "passive"))
      (node (ref "R22") (pin "1") (pinfunction "1_1") (pintype "passive"))
      (node (ref "U$1") (pin "28") (pinfunction "SDA_28") (pintype "bidirectional"))
    )
    (net (code "33") (name "/I2C2_SCL{slash}USART3_TX") (class "Default")
      (node (ref "IC3") (pin "47") (pinfunction "PB10_47") (pintype "bidirectional"))
      (node (ref "J1") (pin "1") (pinfunction "1_1") (pintype "passive"))
      (node (ref "J2") (pin "1") (pinfunction "1_1") (pintype "passive"))
      (node (ref "R25") (pin "1") (pinfunction "1_1") (pintype "passive"))
      (node (ref "XB1") (pin "3") (pinfunction "DIN/~{CONFIG}_3") (pintype "input"))
    )
    (net (code "34") (name "/I2C2_SDA{slash}USART3_RX") (class "Default")
      (node (ref "IC3") (pin "48") (pinfunction "PB11_48") (pintype "bidirectional"))
      (node (ref "J1") (pin "2") (pinfunction "2_2") (pintype "passive"))
      (node (ref "J2") (pin "2") (pinfunction "2_2") (pintype "passive"))
      (node (ref "R24") (pin "1") (pinfunction "1_1") (pintype "passive"))
      (node (ref "XB1") (pin "2") (pinfunction "DOUT_2") (pintype "output"))
    )
    (net (code "35") (name "/LCD_CLK") (class "Default")
      (node (ref "IC3") (pin "69") (pinfunction "PA10_69") (pintype "bidirectional"))
      (node (ref "U$3") (pin "8") (pinfunction "CLK_8") (pintype "bidirectional"))
    )
    (net (code "36") (name "/LCD_DATA") (class "Default")
      (node (ref "IC3") (pin "67") (pinfunction "PA8_67") (pintype "bidirectional"))
      (node (ref "U$3") (pin "1") (pinfunction "A1_1") (pintype "bidirectional"))
      (node (ref "U$3") (pin "2") (pinfunction "A2_2") (pintype "bidirectional"))
    )
    (net (code "37") (name "/LCD_E") (class "Default")
      (node (ref "IC3") (pin "81") (pinfunction "PD0_81") (pintype "bidirectional"))
      (node (ref "LCD") (pin "E") (pinfunction "E_E") (pintype "bidirectional"))
    )
    (net (code "38") (name "/LCD_RS") (class "Default")
      (node (ref "IC3") (pin "82") (pinfunction "PD1_82") (pintype "bidirectional"))
      (node (ref "LCD") (pin "RS") (pinfunction "RS_RS") (pintype "bidirectional"))
    )
    (net (code "39") (name "/LED0") (class "Default")
      (node (ref "IC3") (pin "46") (pinfunction "PE15_46") (pintype "bidirectional"))
      (node (ref "R20") (pin "2") (pinfunction "2_2") (pintype "passive"))
    )
    (net (code "40") (name "/LED1") (class "Default")
      (node (ref "IC3") (pin "85") (pinfunction "PD4_85") (pintype "bidirectional"))
      (node (ref "R21") (pin "2") (pinfunction "2_2") (pintype "passive"))
    )
    (net (code "41") (name "/M0_A") (class "Default")
      (node (ref "IC3") (pin "38") (pinfunction "PE7_38") (pintype "bidirectional"))
      (node (ref "U1") (pin "P$43") (pinfunction "IN1_P$43") (pintype "bidirectional"))
    )
    (net (code "42") (name "/M0_B") (class "Default")
      (node (ref "IC3") (pin "39") (pinfunction "PE8_39") (pintype "bidirectional"))
      (node (ref "U1") (pin "P$42") (pinfunction "IN2_P$42") (pintype "bidirectional"))
    )
    (net (code "43") (name "/M0_EN") (class "Default")
      (node (ref "IC3") (pin "40") (pinfunction "PE9_40") (pintype "bidirectional"))
      (node (ref "U1") (pin "P$3") (pinfunction "EN_D2_P$3") (pintype "bidirectional"))
    )
    (net (code "44") (name "/M0_FAULT") (class "Default")
      (node (ref "IC3") (pin "55") (pinfunction "PD8_55") (pintype "bidirectional"))
      (node (ref "R5") (pin "1") (pinfunction "1_1") (pintype "passive"))
      (node (ref "U1") (pin "P$44") (pinfunction "SFA_P$44") (pintype "bidirectional"))
    )
    (net (code "45") (name "/M0_SENSE") (class "Default")
      (node (ref "C10") (pin "1") (pinfunction "1_1") (pintype "passive"))
      (node (ref "IC3") (pin "35") (pinfunction "PB0_35") (pintype "bidirectional"))
      (node (ref "R8") (pin "2") (pinfunction "2_2") (pintype "passive"))
      (node (ref "U1") (pin "P$2") (pinfunction "FBA_P$2") (pintype "bidirectional"))
    )
    (net (code "46") (name "/M1_A") (class "Default")
      (node (ref "IC3") (pin "41") (pinfunction "PE10_41") (pintype "bidirectional"))
      (node (ref "U1") (pin "P$20") (pinfunction "IN4_P$20") (pintype "bidirectional"))
    )
    (net (code "47") (name "/M1_B") (class "Default")
      (node (ref "IC3") (pin "43") (pinfunction "PE12_43") (pintype "bidirectional"))
      (node (ref "U1") (pin "P$21") (pinfunction "IN3_P$21") (pintype "bidirectional"))
    )
    (net (code "48") (name "/M1_EN") (class "Default")
      (node (ref "IC3") (pin "42") (pinfunction "PE11_42") (pintype "bidirectional"))
      (node (ref "U1") (pin "P$25") (pinfunction "EN_D4_P$25") (pintype "bidirectional"))
    )
    (net (code "49") (name "/M1_FAULT") (class "Default")
      (node (ref "IC3") (pin "56") (pinfunction "PD9_56") (pintype "bidirectional"))
      (node (ref "R6") (pin "2") (pinfunction "2_2") (pintype "passive"))
      (node (ref "U1") (pin "P$22") (pinfunction "SFB_P$22") (pintype "bidirectional"))
    )
    (net (code "50") (name "/M1_SENSE") (class "Default")
      (node (ref "C11") (pin "1") (pinfunction "1_1") (pintype "passive"))
      (node (ref "IC3") (pin "36") (pinfunction "PB1_36") (pintype "bidirectional"))
      (node (ref "R9") (pin "2") (pinfunction "2_2") (pintype "passive"))
      (node (ref "U1") (pin "P$24") (pinfunction "FBB_P$24") (pintype "bidirectional"))
    )
    (net (code "51") (name "/MPOWER") (class "Default")
      (node (ref "C26") (pin "1") (pinfunction "1_1") (pintype "passive"))
      (node (ref "C28") (pin "1") (pinfunction "1_1") (pintype "passive"))
      (node (ref "C31") (pin "1") (pinfunction "1_1") (pintype "passive"))
      (node (ref "C8") (pin "1") (pinfunction "1_1") (pintype "passive"))
      (node (ref "C9") (pin "2") (pinfunction "2_2") (pintype "passive"))
      (node (ref "LED1") (pin "A") (pinfunction "A_A") (pintype "passive"))
      (node (ref "Q5") (pin "10") (pinfunction "D2_10") (pintype "bidirectional"))
      (node (ref "Q5") (pin "5") (pinfunction "D2_5") (pintype "bidirectional"))
      (node (ref "Q5") (pin "6") (pinfunction "D2_6") (pintype "bidirectional"))
      (node (ref "R10") (pin "2") (pinfunction "2_2") (pintype "passive"))
      (node (ref "R18") (pin "1") (pinfunction "1_1") (pintype "passive"))
      (node (ref "R34") (pin "2") (pinfunction "2_2") (pintype "passive"))
      (node (ref "U1") (pin "P$17") (pinfunction "VPWRB_1_P$17") (pintype "bidirectional"))
      (node (ref "U1") (pin "P$18") (pinfunction "VPWRB_2_P$18") (pintype "bidirectional"))
      (node (ref "U1") (pin "P$26") (pinfunction "VPWRB_3_P$26") (pintype "bidirectional"))
      (node (ref "U1") (pin "P$27") (pinfunction "VPWRB_4_P$27") (pintype "bidirectional"))
      (node (ref "U1") (pin "P$28") (pinfunction "VPWRB_5_P$28") (pintype "bidirectional"))
      (node (ref "U1") (pin "P$39") (pinfunction "VPWRA_4_P$39") (pintype "bidirectional"))
      (node (ref "U1") (pin "P$4") (pinfunction "VPWRA_1_P$4") (pintype "bidirectional"))
      (node (ref "U1") (pin "P$40") (pinfunction "VPWRA_5_P$40") (pintype "bidirectional"))
      (node (ref "U1") (pin "P$5") (pinfunction "VPWRA_2_P$5") (pintype "bidirectional"))
      (node (ref "U1") (pin "P$6") (pinfunction "VPWRA_3_P$6") (pintype "bidirectional"))
      (node (ref "U2") (pin "4") (pinfunction "VIN_4") (pintype "bidirectional"))
      (node (ref "U2") (pin "5") (pinfunction "VIN_5") (pintype "bidirectional"))
      (node (ref "U2") (pin "6") (pinfunction "VIN_6") (pintype "bidirectional"))
    )
    (net (code "52") (name "/OUT1") (class "Default")
      (node (ref "LED6") (pin "2") (pinfunction "2_2") (pintype "passive"))
      (node (ref "LED6") (pin "3") (pinfunction "3_3") (pintype "passive"))
      (node (ref "MOTOR0") (pin "L") (pinfunction "L_L") (pintype "bidirectional"))
      (node (ref "U1") (pin "P$7") (pinfunction "OUT1_1_P$7") (pintype "bidirectional"))
      (node (ref "U1") (pin "P$8") (pinfunction "OUT1_2_P$8") (pintype "bidirectional"))
      (node (ref "U1") (pin "P$9") (pinfunction "OUT1_3_P$9") (pintype "bidirectional"))
    )
    (net (code "53") (name "/OUT2") (class "Default")
      (node (ref "MOTOR0") (pin "R") (pinfunction "R_R") (pintype "bidirectional"))
      (node (ref "R37") (pin "1") (pinfunction "1_1") (pintype "passive"))
      (node (ref "U1") (pin "P$36") (pinfunction "OUT2_1_P$36") (pintype "bidirectional"))
      (node (ref "U1") (pin "P$37") (pinfunction "OUT2_2_P$37") (pintype "bidirectional"))
      (node (ref "U1") (pin "P$38") (pinfunction "OUT2_3_P$38") (pintype "bidirectional"))
    )
    (net (code "54") (name "/OUT3") (class "Default")
      (node (ref "LED7") (pin "2") (pinfunction "2_2") (pintype "passive"))
      (node (ref "LED7") (pin "3") (pinfunction "3_3") (pintype "passive"))
      (node (ref "MOTOR1") (pin "L") (pinfunction "L_L") (pintype "bidirectional"))
      (node (ref "U1") (pin "P$29") (pinfunction "OUT3_1_P$29") (pintype "bidirectional"))
      (node (ref "U1") (pin "P$30") (pinfunction "OUT3_2_P$30") (pintype "bidirectional"))
      (node (ref "U1") (pin "P$31") (pinfunction "OUT3_3_P$31") (pintype "bidirectional"))
    )
    (net (code "55") (name "/OUT4") (class "Default")
      (node (ref "MOTOR1") (pin "R") (pinfunction "R_R") (pintype "bidirectional"))
      (node (ref "R38") (pin "1") (pinfunction "1_1") (pintype "passive"))
      (node (ref "U1") (pin "P$14") (pinfunction "OUT4_1_P$14") (pintype "bidirectional"))
      (node (ref "U1") (pin "P$15") (pinfunction "OUT4_2_P$15") (pintype "bidirectional"))
      (node (ref "U1") (pin "P$16") (pinfunction "OUT4_3_P$16") (pintype "bidirectional"))
    )
    (net (code "56") (name "/RAW_SPWR") (class "Default")
      (node (ref "C27") (pin "1") (pinfunction "1_1") (pintype "passive"))
      (node (ref "Q4") (pin "10") (pinfunction "D2_10") (pintype "bidirectional"))
      (node (ref "Q4") (pin "2") (pinfunction "G1_2") (pintype "bidirectional"))
      (node (ref "Q4") (pin "5") (pinfunction "D2_5") (pintype "bidirectional"))
      (node (ref "Q4") (pin "6") (pinfunction "D2_6") (pintype "bidirectional"))
      (node (ref "R29") (pin "1") (pinfunction "1_1") (pintype "passive"))
      (node (ref "R36") (pin "2") (pinfunction "2_2") (pintype "passive"))
      (node (ref "SERVO_PWR") (pin "L") (pinfunction "L_L") (pintype "bidirectional"))
    )
    (net (code "57") (name "/RESET") (class "Default")
      (node (ref "C30") (pin "2") (pinfunction "2_2") (pintype "passive"))
      (node (ref "IC3") (pin "14") (pinfunction "NRST_14") (pintype "input"))
      (node (ref "R7") (pin "1") (pinfunction "1_1") (pintype "passive"))
      (node (ref "RESET") (pin "1") (pinfunction "S_1") (pintype "passive"))
      (node (ref "RESET") (pin "2") (pinfunction "S1_2") (pintype "passive"))
    )
    (net (code "58") (name "/SDIO_CK") (class "Default")
      (node (ref "IC3") (pin "80") (pinfunction "PC12_80") (pintype "bidirectional"))
      (node (ref "SD") (pin "5") (pinfunction "SCK_5") (pintype "bidirectional"))
    )
    (net (code "59") (name "/SDIO_CMD") (class "Default")
      (node (ref "IC3") (pin "83") (pinfunction "PD2_83") (pintype "bidirectional"))
      (node (ref "SD") (pin "3") (pinfunction "DI_3") (pintype "bidirectional"))
    )
    (net (code "60") (name "/SDIO_D0") (class "Default")
      (node (ref "IC3") (pin "65") (pinfunction "PC8_65") (pintype "bidirectional"))
      (node (ref "R13") (pin "2") (pinfunction "2_2") (pintype "passive"))
      (node (ref "SD") (pin "7") (pinfunction "DO_7") (pintype "bidirectional"))
    )
    (net (code "61") (name "/SDIO_D1") (class "Default")
      (node (ref "IC3") (pin "66") (pinfunction "PC9_66") (pintype "bidirectional"))
      (node (ref "R14") (pin "2") (pinfunction "2_2") (pintype "passive"))
      (node (ref "SD") (pin "8") (pinfunction "RSV_8") (pintype "bidirectional"))
    )
    (net (code "62") (name "/SDIO_D2") (class "Default")
      (node (ref "IC3") (pin "78") (pinfunction "PC10_78") (pintype "bidirectional"))
      (node (ref "R15") (pin "1") (pinfunction "1_1") (pintype "passive"))
      (node (ref "SD") (pin "1") (pinfunction "NC_1") (pintype "bidirectional"))
    )
    (net (code "63") (name "/SDIO_D3") (class "Default")
      (node (ref "IC3") (pin "79") (pinfunction "PC11_79") (pintype "bidirectional"))
      (node (ref "R12") (pin "2") (pinfunction "2_2") (pintype "passive"))
      (node (ref "SD") (pin "2") (pinfunction "CS_2") (pintype "bidirectional"))
    )
    (net (code "64") (name "/SERVO0") (class "Default")
      (node (ref "IC3") (pin "44") (pinfunction "PE13_44") (pintype "bidirectional"))
      (node (ref "J16") (pin "8") (pinfunction "8_8") (pintype "passive"))
    )
    (net (code "65") (name "/SERVO1") (class "Default")
      (node (ref "IC3") (pin "45") (pinfunction "PE14_45") (pintype "bidirectional"))
      (node (ref "J16") (pin "7") (pinfunction "7_7") (pintype "passive"))
    )
    (net (code "66") (name "/SERVO2") (class "Default")
      (node (ref "IC3") (pin "59") (pinfunction "PD12_59") (pintype "bidirectional"))
      (node (ref "J16") (pin "6") (pinfunction "6_6") (pintype "passive"))
    )
    (net (code "67") (name "/SERVO3") (class "Default")
      (node (ref "IC3") (pin "60") (pinfunction "PD13_60") (pintype "bidirectional"))
      (node (ref "J16") (pin "5") (pinfunction "5_5") (pintype "passive"))
    )
    (net (code "68") (name "/SERVO4") (class "Default")
      (node (ref "IC3") (pin "61") (pinfunction "PD14_61") (pintype "bidirectional"))
      (node (ref "J16") (pin "4") (pinfunction "4_4") (pintype "passive"))
    )
    (net (code "69") (name "/SERVO5") (class "Default")
      (node (ref "IC3") (pin "62") (pinfunction "PD15_62") (pintype "bidirectional"))
      (node (ref "J16") (pin "3") (pinfunction "3_3") (pintype "passive"))
    )
    (net (code "70") (name "/SERVO6") (class "Default")
      (node (ref "IC3") (pin "63") (pinfunction "PC6_63") (pintype "bidirectional"))
      (node (ref "J16") (pin "2") (pinfunction "2_2") (pintype "passive"))
    )
    (net (code "71") (name "/SERVO7") (class "Default")
      (node (ref "IC3") (pin "64") (pinfunction "PC7_64") (pintype "bidirectional"))
      (node (ref "J16") (pin "1") (pinfunction "1_1") (pintype "passive"))
    )
    (net (code "72") (name "/SERVO_SENSE") (class "Default")
      (node (ref "IC3") (pin "34") (pinfunction "PC5_34") (pintype "bidirectional"))
      (node (ref "R40") (pin "2") (pinfunction "2_2") (pintype "passive"))
      (node (ref "R41") (pin "1") (pinfunction "1_1") (pintype "passive"))
    )
    (net (code "73") (name "/SPI1_MISO") (class "Default")
      (node (ref "IC3") (pin "31") (pinfunction "PA6_31") (pintype "bidirectional"))
      (node (ref "J5") (pin "4") (pinfunction "4_4") (pintype "passive"))
    )
    (net (code "74") (name "/SPI1_MOSI") (class "Default")
      (node (ref "IC3") (pin "32") (pinfunction "PA7_32") (pintype "bidirectional"))
      (node (ref "J5") (pin "3") (pinfunction "3_3") (pintype "passive"))
    )
    (net (code "75") (name "/SPI1_NSS") (class "Default")
      (node (ref "IC3") (pin "29") (pinfunction "PA4_29") (pintype "bidirectional"))
      (node (ref "J5") (pin "2") (pinfunction "2_2") (pintype "passive"))
    )
    (net (code "76") (name "/SPI1_SCK") (class "Default")
      (node (ref "IC3") (pin "30") (pinfunction "PA5_30") (pintype "bidirectional"))
      (node (ref "J5") (pin "5") (pinfunction "5_5") (pintype "passive"))
    )
    (net (code "77") (name "/SPWR") (class "Default")
      (node (ref "J15") (pin "1") (pinfunction "1_1") (pintype "passive"))
      (node (ref "J15") (pin "2") (pinfunction "2_2") (pintype "passive"))
      (node (ref "J15") (pin "3") (pinfunction "3_3") (pintype "passive"))
      (node (ref "J15") (pin "4") (pinfunction "4_4") (pintype "passive"))
      (node (ref "J15") (pin "5") (pinfunction "5_5") (pintype "passive"))
      (node (ref "J15") (pin "6") (pinfunction "6_6") (pintype "passive"))
      (node (ref "J15") (pin "7") (pinfunction "7_7") (pintype "passive"))
      (node (ref "J15") (pin "8") (pinfunction "8_8") (pintype "passive"))
      (node (ref "Q4") (pin "1") (pinfunction "S1_1") (pintype "bidirectional"))
      (node (ref "Q4") (pin "3") (pinfunction "S2_3") (pintype "bidirectional"))
      (node (ref "R40") (pin "1") (pinfunction "1_1") (pintype "passive"))
    )
    (net (code "78") (name "/SWDCLK") (class "Default")
      (node (ref "IC3") (pin "76") (pinfunction "PA14_76") (pintype "bidirectional"))
      (node (ref "J7") (pin "3") (pinfunction "3_3") (pintype "passive"))
    )
    (net (code "79") (name "/SWDIO") (class "Default")
      (node (ref "IC3") (pin "72") (pinfunction "PA13_72") (pintype "bidirectional"))
      (node (ref "J7") (pin "1") (pinfunction "1_1") (pintype "passive"))
    )
    (net (code "80") (name "/USART1_RX") (class "Default")
      (node (ref "IC3") (pin "93") (pinfunction "PB7_93") (pintype "bidirectional"))
      (node (ref "J6") (pin "3") (pinfunction "3_3") (pintype "passive"))
    )
    (net (code "81") (name "/USART1_TX") (class "Default")
      (node (ref "IC3") (pin "92") (pinfunction "PB6_92") (pintype "bidirectional"))
      (node (ref "J6") (pin "2") (pinfunction "2_2") (pintype "passive"))
    )
    (net (code "82") (name "/USART2_RX") (class "Default")
      (node (ref "IC3") (pin "87") (pinfunction "PD6_87") (pintype "bidirectional"))
      (node (ref "J3") (pin "2") (pinfunction "2_2") (pintype "passive"))
    )
    (net (code "83") (name "/USART2_TX") (class "Default")
      (node (ref "IC3") (pin "86") (pinfunction "PD5_86") (pintype "bidirectional"))
      (node (ref "J3") (pin "1") (pinfunction "1_1") (pintype "passive"))
    )
    (net (code "84") (name "/USB_5V") (class "Default")
      (node (ref "C22") (pin "2") (pinfunction "2_2") (pintype "passive"))
      (node (ref "C24") (pin "2") (pinfunction "2_2") (pintype "passive"))
      (node (ref "IC3") (pin "68") (pinfunction "PA9_68") (pintype "bidirectional"))
      (node (ref "Q1") (pin "3") (pinfunction "D_3") (pintype "passive"))
      (node (ref "USB2") (pin "VBUS") (pinfunction "VBUS_VBUS") (pintype "bidirectional"))
    )
    (net (code "85") (name "/USB_DEV_DM") (class "Default")
      (node (ref "C14") (pin "1") (pinfunction "1_1") (pintype "passive"))
      (node (ref "IC3") (pin "70") (pinfunction "PA11_70") (pintype "bidirectional"))
      (node (ref "R46") (pin "2") (pinfunction "2_2") (pintype "passive"))
    )
    (net (code "86") (name "/USB_DEV_DP") (class "Default")
      (node (ref "C13") (pin "1") (pinfunction "1_1") (pintype "passive"))
      (node (ref "IC3") (pin "71") (pinfunction "PA12_71") (pintype "bidirectional"))
      (node (ref "R47") (pin "2") (pinfunction "2_2") (pintype "passive"))
    )
    (net (code "87") (name "/USB_HOST_DM") (class "Default")
      (node (ref "C18") (pin "1") (pinfunction "1_1") (pintype "passive"))
      (node (ref "IC3") (pin "53") (pinfunction "PB14_53") (pintype "bidirectional"))
      (node (ref "R49") (pin "2") (pinfunction "2_2") (pintype "passive"))
    )
    (net (code "88") (name "/USB_HOST_DP") (class "Default")
      (node (ref "C17") (pin "1") (pinfunction "1_1") (pintype "passive"))
      (node (ref "IC3") (pin "54") (pinfunction "PB15_54") (pintype "bidirectional"))
      (node (ref "R48") (pin "2") (pinfunction "2_2") (pintype "passive"))
    )
    (net (code "89") (name "/USB_HOST_EN") (class "Default")
      (node (ref "IC3") (pin "52") (pinfunction "PB13_52") (pintype "bidirectional"))
      (node (ref "U$2") (pin "4") (pinfunction "EN_4") (pintype "bidirectional"))
    )
    (net (code "90") (name "/USB_HOST_FAULT") (class "Default")
      (node (ref "IC3") (pin "51") (pinfunction "PB12_51") (pintype "bidirectional"))
      (node (ref "U$2") (pin "5") (pinfunction "FAULT_5") (pintype "bidirectional"))
    )
    (net (code "91") (name "GND") (class "Default")
      (node (ref "BTN1") (pin "3") (pinfunction "P_3") (pintype "passive"))
      (node (ref "BTN1") (pin "4") (pinfunction "P1_4") (pintype "passive"))
      (node (ref "BTN2") (pin "3") (pinfunction "P_3") (pintype "passive"))
      (node (ref "BTN2") (pin "4") (pinfunction "P1_4") (pintype "passive"))
      (node (ref "C1") (pin "2") (pinfunction "2_2") (pintype "passive"))
      (node (ref "C10") (pin "2") (pinfunction "2_2") (pintype "passive"))
      (node (ref "C11") (pin "2") (pinfunction "2_2") (pintype "passive"))
      (node (ref "C12") (pin "2") (pinfunction "2_2") (pintype "passive"))
      (node (ref "C13") (pin "2") (pinfunction "2_2") (pintype "passive"))
      (node (ref "C14") (pin "2") (pinfunction "2_2") (pintype "passive"))
      (node (ref "C15") (pin "2") (pinfunction "2_2") (pintype "passive"))
      (node (ref "C16") (pin "2") (pinfunction "2_2") (pintype "passive"))
      (node (ref "C17") (pin "2") (pinfunction "2_2") (pintype "passive"))
      (node (ref "C18") (pin "2") (pinfunction "2_2") (pintype "passive"))
      (node (ref "C21") (pin "2") (pinfunction "2_2") (pintype "passive"))
      (node (ref "C22") (pin "1") (pinfunction "1_1") (pintype "passive"))
      (node (ref "C23") (pin "2") (pinfunction "2_2") (pintype "passive"))
      (node (ref "C24") (pin "1") (pinfunction "1_1") (pintype "passive"))
      (node (ref "C25") (pin "2") (pinfunction "2_2") (pintype "passive"))
      (node (ref "C26") (pin "2") (pinfunction "2_2") (pintype "passive"))
      (node (ref "C27") (pin "2") (pinfunction "2_2") (pintype "passive"))
      (node (ref "C28") (pin "2") (pinfunction "2_2") (pintype "passive"))
      (node (ref "C3") (pin "2") (pinfunction "2_2") (pintype "passive"))
      (node (ref "C31") (pin "2") (pinfunction "2_2") (pintype "passive"))
      (node (ref "C33") (pin "1") (pinfunction "1_1") (pintype "passive"))
      (node (ref "C34") (pin "2") (pinfunction "2_2") (pintype "passive"))
      (node (ref "C35") (pin "2") (pinfunction "2_2") (pintype "passive"))
      (node (ref "C36") (pin "2") (pinfunction "2_2") (pintype "passive"))
      (node (ref "C37") (pin "2") (pinfunction "2_2") (pintype "passive"))
      (node (ref "C39") (pin "2") (pinfunction "2_2") (pintype "passive"))
      (node (ref "C4") (pin "2") (pinfunction "2_2") (pintype "passive"))
      (node (ref "C40") (pin "2") (pinfunction "2_2") (pintype "passive"))
      (node (ref "C41") (pin "2") (pinfunction "2_2") (pintype "passive"))
      (node (ref "C42") (pin "2") (pinfunction "2_2") (pintype "passive"))
      (node (ref "C43") (pin "2") (pinfunction "2_2") (pintype "passive"))
      (node (ref "C44") (pin "-") (pinfunction "-_-") (pintype "passive"))
      (node (ref "C46") (pin "2") (pinfunction "2_2") (pintype "passive"))
      (node (ref "C47") (pin "2") (pinfunction "2_2") (pintype "passive"))
      (node (ref "C5") (pin "2") (pinfunction "2_2") (pintype "passive"))
      (node (ref "C6") (pin "2") (pinfunction "2_2") (pintype "passive"))
      (node (ref "C7") (pin "2") (pinfunction "2_2") (pintype "passive"))
      (node (ref "IC3") (pin "10") (pinfunction "VSS_5_10") (pintype "power_in"))
      (node (ref "IC3") (pin "20") (pinfunction "VSSA_20") (pintype "power_in"))
      (node (ref "IC3") (pin "27") (pinfunction "VSS_4_27") (pintype "power_in"))
      (node (ref "IC3") (pin "74") (pinfunction "VSS_2_74") (pintype "power_in"))
      (node (ref "IC3") (pin "99") (pinfunction "PDR_ON_99") (pintype "power_in"))
      (node (ref "IC4") (pin "4") (pinfunction "V-_4") (pintype "power_in"))
      (node (ref "J1") (pin "3") (pinfunction "3_3") (pintype "passive"))
      (node (ref "J11") (pin "1") (pinfunction "1_1") (pintype "passive"))
      (node (ref "J11") (pin "10") (pinfunction "10_10") (pintype "passive"))
      (node (ref "J11") (pin "11") (pinfunction "11_11") (pintype "passive"))
      (node (ref "J11") (pin "12") (pinfunction "12_12") (pintype "passive"))
      (node (ref "J11") (pin "13") (pinfunction "13_13") (pintype "passive"))
      (node (ref "J11") (pin "14") (pinfunction "14_14") (pintype "passive"))
      (node (ref "J11") (pin "15") (pinfunction "15_15") (pintype "passive"))
      (node (ref "J11") (pin "2") (pinfunction "2_2") (pintype "passive"))
      (node (ref "J11") (pin "3") (pinfunction "3_3") (pintype "passive"))
      (node (ref "J11") (pin "4") (pinfunction "4_4") (pintype "passive"))
      (node (ref "J11") (pin "5") (pinfunction "5_5") (pintype "passive"))
      (node (ref "J11") (pin "6") (pinfunction "6_6") (pintype "passive"))
      (node (ref "J11") (pin "7") (pinfunction "7_7") (pintype "passive"))
      (node (ref "J11") (pin "8") (pinfunction "8_8") (pintype "passive"))
      (node (ref "J11") (pin "9") (pinfunction "9_9") (pintype "passive"))
      (node (ref "J14") (pin "1") (pinfunction "1_1") (pintype "passive"))
      (node (ref "J14") (pin "2") (pinfunction "2_2") (pintype "passive"))
      (node (ref "J14") (pin "3") (pinfunction "3_3") (pintype "passive"))
      (node (ref "J14") (pin "4") (pinfunction "4_4") (pintype "passive"))
      (node (ref "J14") (pin "5") (pinfunction "5_5") (pintype "passive"))
      (node (ref "J14") (pin "6") (pinfunction "6_6") (pintype "passive"))
      (node (ref "J14") (pin "7") (pinfunction "7_7") (pintype "passive"))
      (node (ref "J14") (pin "8") (pinfunction "8_8") (pintype "passive"))
      (node (ref "J17") (pin "3") (pinfunction "3_3") (pintype "passive"))
      (node (ref "J2") (pin "3") (pinfunction "3_3") (pintype "passive"))
      (node (ref "J3") (pin "3") (pinfunction "3_3") (pintype "passive"))
      (node (ref "J4") (pin "3") (pinfunction "3_3") (pintype "passive"))
      (node (ref "J5") (pin "1") (pinfunction "1_1") (pintype "passive"))
      (node (ref "J6") (pin "4") (pinfunction "4_4") (pintype "passive"))
      (node (ref "J7") (pin "2") (pinfunction "2_2") (pintype "passive"))
      (node (ref "J8") (pin "1") (pinfunction "1_1") (pintype "passive"))
      (node (ref "J8") (pin "2") (pinfunction "2_2") (pintype "passive"))
      (node (ref "J8") (pin "3") (pinfunction "3_3") (pintype "passive"))
      (node (ref "J8") (pin "4") (pinfunction "4_4") (pintype "passive"))
      (node (ref "J8") (pin "5") (pinfunction "5_5") (pintype "passive"))
      (node (ref "J8") (pin "6") (pinfunction "6_6") (pintype "passive"))
      (node (ref "J8") (pin "7") (pinfunction "7_7") (pintype "passive"))
      (node (ref "J8") (pin "8") (pinfunction "8_8") (pintype "passive"))
      (node (ref "LCD") (pin "K") (pinfunction "K_K") (pintype "bidirectional"))
      (node (ref "LCD") (pin "R/W") (pinfunction "R/W_R/W") (pintype "bidirectional"))
      (node (ref "LCD") (pin "VSS") (pinfunction "VSS_VSS") (pintype "bidirectional"))
      (node (ref "LED2") (pin "C") (pinfunction "C_C") (pintype "passive"))
      (node (ref "LED3") (pin "C") (pinfunction "C_C") (pintype "passive"))
      (node (ref "LED4") (pin "C") (pinfunction "C_C") (pintype "passive"))
      (node (ref "POT") (pin "3") (pinfunction "E_3") (pintype "passive"))
      (node (ref "POWER") (pin "R") (pinfunction "R_R") (pintype "bidirectional"))
      (node (ref "Q2") (pin "2") (pinfunction "E_2") (pintype "passive"))
      (node (ref "Q3") (pin "1") (pinfunction "S_1") (pintype "bidirectional"))
      (node (ref "Q3") (pin "2") (pinfunction "S_2") (pintype "bidirectional"))
      (node (ref "Q3") (pin "3") (pinfunction "S_3") (pintype "bidirectional"))
      (node (ref "R11") (pin "1") (pinfunction "1_1") (pintype "passive"))
      (node (ref "R19") (pin "2") (pinfunction "2_2") (pintype "passive"))
      (node (ref "R2") (pin "2") (pinfunction "2_2") (pintype "passive"))
      (node (ref "R26") (pin "1") (pinfunction "1_1") (pintype "passive"))
      (node (ref "R28") (pin "2") (pinfunction "2_2") (pintype "passive"))
      (node (ref "R30") (pin "1") (pinfunction "1_1") (pintype "passive"))
      (node (ref "R33") (pin "1") (pinfunction "1_1") (pintype "passive"))
      (node (ref "R35") (pin "1") (pinfunction "1_1") (pintype "passive"))
      (node (ref "R41") (pin "2") (pinfunction "2_2") (pintype "passive"))
      (node (ref "R42") (pin "1") (pinfunction "1_1") (pintype "passive"))
      (node (ref "R43") (pin "1") (pinfunction "1_1") (pintype "passive"))
      (node (ref "R44") (pin "1") (pinfunction "1_1") (pintype "passive"))
      (node (ref "R8") (pin "1") (pinfunction "1_1") (pintype "passive"))
      (node (ref "R9") (pin "1") (pinfunction "1_1") (pintype "passive"))
      (node (ref "RESET") (pin "3") (pinfunction "P_3") (pintype "passive"))
      (node (ref "RESET") (pin "4") (pinfunction "P1_4") (pintype "passive"))
      (node (ref "SD") (pin "6") (pinfunction "GND_6") (pintype "bidirectional"))
      (node (ref "SD") (pin "GND1") (pinfunction "SHIELD_GND1") (pintype "bidirectional"))
      (node (ref "SD") (pin "GND3") (pinfunction "SHIELD_GND3") (pintype "bidirectional"))
      (node (ref "SERVO_PWR") (pin "R") (pinfunction "R_R") (pintype "bidirectional"))
      (node (ref "SW1") (pin "P$2") (pinfunction "P$2_P$2") (pintype "bidirectional"))
      (node (ref "U$1") (pin "1") (pinfunction "GND_1") (pintype "bidirectional"))
      (node (ref "U$1") (pin "2") (pinfunction "GND_2") (pintype "bidirectional"))
      (node (ref "U$1") (pin "26") (pinfunction "SA0_26") (pintype "bidirectional"))
      (node (ref "U$1") (pin "27") (pinfunction "SA0_27") (pintype "bidirectional"))
      (node (ref "U$1") (pin "3") (pinfunction "GND_3") (pintype "bidirectional"))
      (node (ref "U$1") (pin "4") (pinfunction "GND_4") (pintype "bidirectional"))
      (node (ref "U$1") (pin "5") (pinfunction "GND_5") (pintype "bidirectional"))
      (node (ref "U$1") (pin "6") (pinfunction "GND_6") (pintype "bidirectional"))
      (node (ref "U$2") (pin "1") (pinfunction "GND_1") (pintype "bidirectional"))
      (node (ref "U$3") (pin "7") (pinfunction "GND_7") (pintype "bidirectional"))
      (node (ref "U1") (pin "P$1") (pinfunction "D1_P$1") (pintype "bidirectional"))
      (node (ref "U1") (pin "P$10") (pinfunction "PGNDA_1_P$10") (pintype "bidirectional"))
      (node (ref "U1") (pin "P$11") (pinfunction "PGNDA_2_P$11") (pintype "bidirectional"))
      (node (ref "U1") (pin "P$12") (pinfunction "PGNDB_1_P$12") (pintype "bidirectional"))
      (node (ref "U1") (pin "P$13") (pinfunction "PGNDB_2_P$13") (pintype "bidirectional"))
      (node (ref "U1") (pin "P$23") (pinfunction "D3_P$23") (pintype "bidirectional"))
      (node (ref "U1") (pin "P$32") (pinfunction "PGNDB_3_P$32") (pintype "bidirectional"))
      (node (ref "U1") (pin "P$33") (pinfunction "PGNDB_4_P$33") (pintype "bidirectional"))
      (node (ref "U1") (pin "P$34") (pinfunction "PGNDA_3_P$34") (pintype "bidirectional"))
      (node (ref "U1") (pin "P$35") (pinfunction "PGNDA_4_P$35") (pintype "bidirectional"))
      (node (ref "U1") (pin "P$45") (pinfunction "GND_P$45") (pintype "bidirectional"))
      (node (ref "U1") (pin "P$46") (pinfunction "GND_P$46") (pintype "bidirectional"))
      (node (ref "U1") (pin "P$47") (pinfunction "GND_P$47") (pintype "bidirectional"))
      (node (ref "U10") (pin "GND") (pinfunction "GND_GND") (pintype "bidirectional"))
      (node (ref "U2") (pin "14") (pinfunction "GND_14") (pintype "bidirectional"))
      (node (ref "U2") (pin "P$1") (pinfunction "GND_P$1") (pintype "bidirectional"))
      (node (ref "U3") (pin "3") (pinfunction "GND_3") (pintype "bidirectional"))
      (node (ref "U6") (pin "P$2") (pinfunction "GND_P$2") (pintype "bidirectional"))
      (node (ref "U8") (pin "P$2") (pinfunction "GND_P$2") (pintype "bidirectional"))
      (node (ref "USB1") (pin "GND") (pinfunction "GND_GND") (pintype "bidirectional"))
      (node (ref "USB1") (pin "GND@1") (pinfunction "GND_GND@1") (pintype "bidirectional"))
      (node (ref "USB1") (pin "GND@2") (pinfunction "GND_GND@2") (pintype "bidirectional"))
      (node (ref "USB2") (pin "GND") (pinfunction "GND_GND") (pintype "bidirectional"))
      (node (ref "USB2") (pin "MTN1") (pinfunction "MTN2_MTN1") (pintype "bidirectional"))
      (node (ref "USB2") (pin "MTN2") (pinfunction "MTN3_MTN2") (pintype "bidirectional"))
      (node (ref "USB2") (pin "MTN3") (pinfunction "MTN1_MTN3") (pintype "bidirectional"))
      (node (ref "USB2") (pin "MTN4") (pinfunction "MTN4_MTN4") (pintype "bidirectional"))
      (node (ref "XB1") (pin "10") (pinfunction "GND_10") (pintype "power_in"))
      (node (ref "Y1") (pin "2") (pinfunction "2_2") (pintype "passive"))
    )
    (net (code "92") (name "Net-(C21-Pad1)") (class "Default")
      (node (ref "C21") (pin "1") (pinfunction "1_1") (pintype "passive"))
      (node (ref "C23") (pin "1") (pinfunction "1_1") (pintype "passive"))
      (node (ref "U$2") (pin "6") (pinfunction "VOUT_6") (pintype "bidirectional"))
      (node (ref "U$2") (pin "7") (pinfunction "VOUT_7") (pintype "bidirectional"))
      (node (ref "U$2") (pin "8") (pinfunction "VOUT_8") (pintype "bidirectional"))
      (node (ref "USB1") (pin "VBUS") (pinfunction "VBUS_VBUS") (pintype "bidirectional"))
    )
    (net (code "93") (name "Net-(C38-Pad2)") (class "Default")
      (node (ref "C38") (pin "2") (pinfunction "2_2") (pintype "passive"))
      (node (ref "R44") (pin "2") (pinfunction "2_2") (pintype "passive"))
      (node (ref "R45") (pin "1") (pinfunction "1_1") (pintype "passive"))
      (node (ref "U10") (pin "ADJ") (pinfunction "ADJ_ADJ") (pintype "bidirectional"))
    )
    (net (code "94") (name "Net-(IC3A-VCAP_2)") (class "Default")
      (node (ref "C37") (pin "1") (pinfunction "1_1") (pintype "passive"))
      (node (ref "IC3") (pin "73") (pinfunction "VCAP_2_73") (pintype "power_in"))
    )
    (net (code "95") (name "Net-(IC3B-OSC_IN)") (class "Default")
      (node (ref "IC3") (pin "12") (pinfunction "OSC_IN_12") (pintype "input"))
      (node (ref "Y1") (pin "3") (pinfunction "3_3") (pintype "passive"))
    )
    (net (code "96") (name "Net-(IC3B-OSC_OUT)") (class "Default")
      (node (ref "IC3") (pin "13") (pinfunction "OSC_OUT_13") (pintype "output"))
      (node (ref "Y1") (pin "1") (pinfunction "1_1") (pintype "passive"))
    )
    (net (code "97") (name "Net-(IC3M-VCAP_1)") (class "Default")
      (node (ref "C7") (pin "1") (pinfunction "1_1") (pintype "passive"))
      (node (ref "IC3") (pin "49") (pinfunction "VCAP_1_49") (pintype "power_in"))
    )
    (net (code "98") (name "Net-(IC3N-BOOT0)") (class "Default")
      (node (ref "IC3") (pin "94") (pinfunction "BOOT0_94") (pintype "input"))
      (node (ref "R42") (pin "2") (pinfunction "2_2") (pintype "passive"))
    )
    (net (code "99") (name "Net-(IC4A-+IN)") (class "Default")
      (node (ref "IC4") (pin "3") (pinfunction "+IN_3") (pintype "input"))
      (node (ref "R10") (pin "1") (pinfunction "1_1") (pintype "passive"))
      (node (ref "R11") (pin "2") (pinfunction "2_2") (pintype "passive"))
    )
    (net (code "100") (name "Net-(IC4A-OUT)") (class "Default")
      (node (ref "IC4") (pin "1") (pinfunction "OUT_1") (pintype "output"))
      (node (ref "Q1") (pin "1") (pinfunction "G_1") (pintype "passive"))
    )
    (net (code "101") (name "Net-(IC4B-+IN)") (class "Default")
      (node (ref "IC4") (pin "5") (pinfunction "+IN_5") (pintype "input"))
      (node (ref "R28") (pin "1") (pinfunction "1_1") (pintype "passive"))
      (node (ref "R29") (pin "2") (pinfunction "2_2") (pintype "passive"))
    )
    (net (code "102") (name "Net-(IC4B--IN)") (class "Default")
      (node (ref "IC4") (pin "6") (pinfunction "-IN_6") (pintype "input"))
      (node (ref "R26") (pin "2") (pinfunction "2_2") (pintype "passive"))
      (node (ref "R27") (pin "1") (pinfunction "1_1") (pintype "passive"))
    )
    (net (code "103") (name "Net-(IC4B-OUT)") (class "Default")
      (node (ref "IC4") (pin "7") (pinfunction "OUT_7") (pintype "output"))
      (node (ref "R36") (pin "1") (pinfunction "1_1") (pintype "passive"))
      (node (ref "U3") (pin "2") (pinfunction "A_2") (pintype "bidirectional"))
    )
    (net (code "104") (name "Net-(J12-Pad1)") (class "Default")
      (node (ref "J12") (pin "1") (pinfunction "1_1") (pintype "passive"))
      (node (ref "J12") (pin "10") (pinfunction "10_10") (pintype "passive"))
      (node (ref "J12") (pin "11") (pinfunction "11_11") (pintype "passive"))
      (node (ref "J12") (pin "12") (pinfunction "12_12") (pintype "passive"))
      (node (ref "J12") (pin "13") (pinfunction "13_13") (pintype "passive"))
      (node (ref "J12") (pin "14") (pinfunction "14_14") (pintype "passive"))
      (node (ref "J12") (pin "15") (pinfunction "15_15") (pintype "passive"))
      (node (ref "J12") (pin "2") (pinfunction "2_2") (pintype "passive"))
      (node (ref "J12") (pin "3") (pinfunction "3_3") (pintype "passive"))
      (node (ref "J12") (pin "4") (pinfunction "4_4") (pintype "passive"))
      (node (ref "J12") (pin "5") (pinfunction "5_5") (pintype "passive"))
      (node (ref "J12") (pin "6") (pinfunction "6_6") (pintype "passive"))
      (node (ref "J12") (pin "7") (pinfunction "7_7") (pintype "passive"))
      (node (ref "J12") (pin "8") (pinfunction "8_8") (pintype "passive"))
      (node (ref "J12") (pin "9") (pinfunction "9_9") (pintype "passive"))
      (node (ref "JP2") (pin "2") (pinfunction "2_2") (pintype "passive"))
    )
    (net (code "105") (name "Net-(L1-1)") (class "Default")
      (node (ref "C32") (pin "2") (pinfunction "2_2") (pintype "passive"))
      (node (ref "L1") (pin "P$1") (pinfunction "1_P$1") (pintype "passive"))
      (node (ref "Q3") (pin "5") (pinfunction "D_5") (pintype "bidirectional"))
      (node (ref "Q3") (pin "6") (pinfunction "D_6") (pintype "bidirectional"))
      (node (ref "Q3") (pin "7") (pinfunction "D_7") (pintype "bidirectional"))
      (node (ref "Q3") (pin "8") (pinfunction "D_8") (pintype "bidirectional"))
      (node (ref "U2") (pin "10") (pinfunction "SW_10") (pintype "bidirectional"))
      (node (ref "U2") (pin "8") (pinfunction "SW_8") (pintype "bidirectional"))
      (node (ref "U2") (pin "9") (pinfunction "SW_9") (pintype "bidirectional"))
    )
    (net (code "106") (name "Net-(LCD-PadA)") (class "Default")
      (node (ref "LCD") (pin "A") (pinfunction "A_A") (pintype "bidirectional"))
      (node (ref "R1") (pin "1") (pinfunction "1_1") (pintype "passive"))
    )
    (net (code "107") (name "Net-(LED1-PadC)") (class "Default")
      (node (ref "LED1") (pin "C") (pinfunction "C_C") (pintype "passive"))
      (node (ref "R30") (pin "2") (pinfunction "2_2") (pintype "passive"))
    )
    (net (code "108") (name "Net-(LED2-PadA)") (class "Default")
      (node (ref "LED2") (pin "A") (pinfunction "A_A") (pintype "passive"))
      (node (ref "R20") (pin "1") (pinfunction "1_1") (pintype "passive"))
    )
    (net (code "109") (name "Net-(LED3-PadA)") (class "Default")
      (node (ref "LED3") (pin "A") (pinfunction "A_A") (pintype "passive"))
      (node (ref "R21") (pin "1") (pinfunction "1_1") (pintype "passive"))
    )
    (net (code "110") (name "Net-(LED4-PadA)") (class "Default")
      (node (ref "LED4") (pin "A") (pinfunction "A_A") (pintype "passive"))
      (node (ref "R4") (pin "1") (pinfunction "1_1") (pintype "passive"))
    )
    (net (code "111") (name "Net-(LED5-PadC)") (class "Default")
      (node (ref "LED5") (pin "C") (pinfunction "C_C") (pintype "passive"))
      (node (ref "R35") (pin "2") (pinfunction "2_2") (pintype "passive"))
    )
    (net (code "112") (name "Net-(LED6-Pad1)") (class "Default")
      (node (ref "LED6") (pin "1") (pinfunction "1_1") (pintype "passive"))
      (node (ref "LED6") (pin "4") (pinfunction "4_4") (pintype "passive"))
      (node (ref "R37") (pin "2") (pinfunction "2_2") (pintype "passive"))
    )
    (net (code "113") (name "Net-(LED7-Pad1)") (class "Default")
      (node (ref "LED7") (pin "1") (pinfunction "1_1") (pintype "passive"))
      (node (ref "LED7") (pin "4") (pinfunction "4_4") (pintype "passive"))
      (node (ref "R38") (pin "2") (pinfunction "2_2") (pintype "passive"))
    )
    (net (code "114") (name "Net-(POT-S)") (class "Default")
      (node (ref "LCD") (pin "VO") (pinfunction "VO_VO") (pintype "bidirectional"))
      (node (ref "POT") (pin "2") (pinfunction "S_2") (pintype "passive"))
    )
    (net (code "115") (name "Net-(POWER-PadL)") (class "Default")
      (node (ref "POWER") (pin "L") (pinfunction "L_L") (pintype "bidirectional"))
      (node (ref "Q5") (pin "7") (pinfunction "D1_7") (pintype "bidirectional"))
      (node (ref "Q5") (pin "8") (pinfunction "D1_8") (pintype "bidirectional"))
      (node (ref "Q5") (pin "9") (pinfunction "D1_9") (pintype "bidirectional"))
    )
    (net (code "116") (name "Net-(Q1-S)") (class "Default")
      (node (ref "F1") (pin "1") (pinfunction "1_1") (pintype "bidirectional"))
      (node (ref "Q1") (pin "2") (pinfunction "S_2") (pintype "passive"))
    )
    (net (code "117") (name "Net-(Q2-B)") (class "Default")
      (node (ref "Q2") (pin "1") (pinfunction "B_1") (pintype "passive"))
      (node (ref "R39") (pin "2") (pinfunction "2_2") (pintype "passive"))
    )
    (net (code "118") (name "Net-(Q2-C)") (class "Default")
      (node (ref "Q2") (pin "3") (pinfunction "C_3") (pintype "passive"))
      (node (ref "R17") (pin "2") (pinfunction "2_2") (pintype "passive"))
      (node (ref "SG1") (pin "-") (pinfunction "2_-") (pintype "passive"))
    )
    (net (code "119") (name "Net-(Q3-G)") (class "Default")
      (node (ref "Q3") (pin "4") (pinfunction "G_4") (pintype "bidirectional"))
      (node (ref "U2") (pin "13") (pinfunction "BG_13") (pintype "bidirectional"))
    )
    (net (code "120") (name "Net-(Q4-G2)") (class "Default")
      (node (ref "Q4") (pin "4") (pinfunction "G2_4") (pintype "bidirectional"))
      (node (ref "U3") (pin "4") (pinfunction "Y_4") (pintype "bidirectional"))
    )
    (net (code "121") (name "Net-(Q5-G1)") (class "Default")
      (node (ref "C29") (pin "2") (pinfunction "2_2") (pintype "passive"))
      (node (ref "Q5") (pin "2") (pinfunction "G1_2") (pintype "bidirectional"))
      (node (ref "R2") (pin "1") (pinfunction "1_1") (pintype "passive"))
      (node (ref "ZD1") (pin "P$1") (pinfunction "A_P$1") (pintype "passive"))
    )
    (net (code "122") (name "Net-(Q5-G2)") (class "Default")
      (node (ref "Q5") (pin "4") (pinfunction "G2_4") (pintype "bidirectional"))
      (node (ref "R3") (pin "1") (pinfunction "1_1") (pintype "passive"))
      (node (ref "R31") (pin "1") (pinfunction "1_1") (pintype "passive"))
      (node (ref "ZD2") (pin "P$1") (pinfunction "A_P$1") (pintype "passive"))
    )
    (net (code "123") (name "Net-(Q5-S1)") (class "Default")
      (node (ref "C29") (pin "1") (pinfunction "1_1") (pintype "passive"))
      (node (ref "Q5") (pin "1") (pinfunction "S1_1") (pintype "bidirectional"))
      (node (ref "Q5") (pin "3") (pinfunction "S2_3") (pintype "bidirectional"))
      (node (ref "R3") (pin "2") (pinfunction "2_2") (pintype "passive"))
      (node (ref "ZD1") (pin "P$2") (pinfunction "C_P$2") (pintype "passive"))
      (node (ref "ZD2") (pin "P$2") (pinfunction "C_P$2") (pintype "passive"))
    )
    (net (code "124") (name "Net-(R31-Pad2)") (class "Default")
      (node (ref "R31") (pin "2") (pinfunction "2_2") (pintype "passive"))
      (node (ref "SW1") (pin "P$1") (pinfunction "P$1_P$1") (pintype "bidirectional"))
    )
    (net (code "125") (name "Net-(U$1-CAP)") (class "Default")
      (node (ref "C35") (pin "1") (pinfunction "1_1") (pintype "passive"))
      (node (ref "U$1") (pin "15") (pinfunction "CAP_15") (pintype "bidirectional"))
    )
    (net (code "126") (name "Net-(U$3-QA)") (class "Default")
      (node (ref "LCD") (pin "DB0") (pinfunction "DB0_DB0") (pintype "bidirectional"))
      (node (ref "U$3") (pin "3") (pinfunction "QA_3") (pintype "bidirectional"))
    )
    (net (code "127") (name "Net-(U$3-QB)") (class "Default")
      (node (ref "LCD") (pin "DB1") (pinfunction "DB1_DB1") (pintype "bidirectional"))
      (node (ref "U$3") (pin "4") (pinfunction "QB_4") (pintype "bidirectional"))
    )
    (net (code "128") (name "Net-(U$3-QC)") (class "Default")
      (node (ref "LCD") (pin "DB2") (pinfunction "DB2_DB2") (pintype "bidirectional"))
      (node (ref "U$3") (pin "5") (pinfunction "QC_5") (pintype "bidirectional"))
    )
    (net (code "129") (name "Net-(U$3-QD)") (class "Default")
      (node (ref "LCD") (pin "DB3") (pinfunction "DB3_DB3") (pintype "bidirectional"))
      (node (ref "U$3") (pin "6") (pinfunction "QD_6") (pintype "bidirectional"))
    )
    (net (code "130") (name "Net-(U$3-QE)") (class "Default")
      (node (ref "LCD") (pin "DB4") (pinfunction "DB4_DB4") (pintype "bidirectional"))
      (node (ref "U$3") (pin "10") (pinfunction "QE_10") (pintype "bidirectional"))
    )
    (net (code "131") (name "Net-(U$3-QF)") (class "Default")
      (node (ref "LCD") (pin "DB5") (pinfunction "DB5_DB5") (pintype "bidirectional"))
      (node (ref "U$3") (pin "11") (pinfunction "QF_11") (pintype "bidirectional"))
    )
    (net (code "132") (name "Net-(U$3-QG)") (class "Default")
      (node (ref "LCD") (pin "DB6") (pinfunction "DB6_DB6") (pintype "bidirectional"))
      (node (ref "U$3") (pin "12") (pinfunction "QG_12") (pintype "bidirectional"))
    )
    (net (code "133") (name "Net-(U$3-QH)") (class "Default")
      (node (ref "LCD") (pin "DB7") (pinfunction "DB7_DB7") (pintype "bidirectional"))
      (node (ref "U$3") (pin "13") (pinfunction "QH_13") (pintype "bidirectional"))
    )
    (net (code "134") (name "Net-(U1-CCPA)") (class "Default")
      (node (ref "C9") (pin "1") (pinfunction "1_1") (pintype "passive"))
      (node (ref "U1") (pin "P$41") (pinfunction "CCPA_P$41") (pintype "bidirectional"))
    )
    (net (code "135") (name "Net-(U1-CCPB)") (class "Default")
      (node (ref "C8") (pin "2") (pinfunction "2_2") (pintype "passive"))
      (node (ref "U1") (pin "P$19") (pinfunction "CCPB_P$19") (pintype "bidirectional"))
    )
    (net (code "136") (name "Net-(U2-BOOT)") (class "Default")
      (node (ref "C32") (pin "1") (pinfunction "1_1") (pintype "passive"))
      (node (ref "U2") (pin "11") (pinfunction "BOOT_11") (pintype "bidirectional"))
    )
    (net (code "137") (name "Net-(U2-EN{slash}SYNC)") (class "Default")
      (node (ref "R34") (pin "1") (pinfunction "1_1") (pintype "passive"))
      (node (ref "U2") (pin "3") (pinfunction "EN/SYNC_3") (pintype "bidirectional"))
    )
    (net (code "138") (name "Net-(U2-FB)") (class "Default")
      (node (ref "R32") (pin "1") (pinfunction "1_1") (pintype "passive"))
      (node (ref "R33") (pin "2") (pinfunction "2_2") (pintype "passive"))
      (node (ref "U2") (pin "1") (pinfunction "FB_1") (pintype "bidirectional"))
    )
    (net (code "139") (name "Net-(U2-VCC)") (class "Default")
      (node (ref "C33") (pin "2") (pinfunction "2_2") (pintype "passive"))
      (node (ref "U2") (pin "12") (pinfunction "VCC_12") (pintype "bidirectional"))
    )
    (net (code "140") (name "Net-(U6-IO1_1)") (class "Default")
      (node (ref "U6") (pin "P$1") (pinfunction "IO1_1_P$1") (pintype "bidirectional"))
      (node (ref "USB1") (pin "D-") (pinfunction "D-_D-") (pintype "bidirectional"))
    )
    (net (code "141") (name "Net-(U6-IO1_2)") (class "Default")
      (node (ref "R49") (pin "1") (pinfunction "1_1") (pintype "passive"))
      (node (ref "U6") (pin "P$6") (pinfunction "IO1_2_P$6") (pintype "bidirectional"))
    )
    (net (code "142") (name "Net-(U6-IO2_1)") (class "Default")
      (node (ref "U6") (pin "P$3") (pinfunction "IO2_1_P$3") (pintype "bidirectional"))
      (node (ref "USB1") (pin "D+") (pinfunction "D+_D+") (pintype "bidirectional"))
    )
    (net (code "143") (name "Net-(U6-IO2_2)") (class "Default")
      (node (ref "R48") (pin "1") (pinfunction "1_1") (pintype "passive"))
      (node (ref "U6") (pin "P$4") (pinfunction "IO2_2_P$4") (pintype "bidirectional"))
    )
    (net (code "144") (name "Net-(U8-IO1_1)") (class "Default")
      (node (ref "U8") (pin "P$1") (pinfunction "IO1_1_P$1") (pintype "bidirectional"))
      (node (ref "USB2") (pin "D-") (pinfunction "D-_D-") (pintype "bidirectional"))
    )
    (net (code "145") (name "Net-(U8-IO1_2)") (class "Default")
      (node (ref "R46") (pin "1") (pinfunction "1_1") (pintype "passive"))
      (node (ref "U8") (pin "P$6") (pinfunction "IO1_2_P$6") (pintype "bidirectional"))
    )
    (net (code "146") (name "Net-(U8-IO2_1)") (class "Default")
      (node (ref "U8") (pin "P$3") (pinfunction "IO2_1_P$3") (pintype "bidirectional"))
      (node (ref "USB2") (pin "D+") (pinfunction "D+_D+") (pintype "bidirectional"))
    )
    (net (code "147") (name "Net-(U8-IO2_2)") (class "Default")
      (node (ref "R47") (pin "1") (pinfunction "1_1") (pintype "passive"))
      (node (ref "U8") (pin "P$4") (pinfunction "IO2_2_P$4") (pintype "bidirectional"))
    )
    (net (code "148") (name "Net-(XB1-PWM0{slash}RSSI)") (class "Default")
      (node (ref "LED5") (pin "A") (pinfunction "A_A") (pintype "passive"))
      (node (ref "XB1") (pin "6") (pinfunction "PWM0/RSSI_6") (pintype "output"))
    )
    (net (code "149") (name "unconnected-(J6-Pad1)") (class "Default")
      (node (ref "J6") (pin "1") (pinfunction "1_1") (pintype "passive"))
    )
    (net (code "150") (name "unconnected-(J6-Pad6)") (class "Default")
      (node (ref "J6") (pin "6") (pinfunction "6_6") (pintype "passive"))
    )
    (net (code "151") (name "unconnected-(SD-SHIELD-PadCD1)") (class "Default")
      (node (ref "SD") (pin "CD1") (pinfunction "SHIELD_CD1") (pintype "bidirectional"))
    )
    (net (code "152") (name "unconnected-(SD-SHIELD-PadCD2)") (class "Default")
      (node (ref "SD") (pin "CD2") (pinfunction "SHIELD_CD2") (pintype "bidirectional"))
    )
    (net (code "153") (name "unconnected-(U2-PGOOD-Pad2)") (class "Default")
      (node (ref "U2") (pin "2") (pinfunction "PGOOD_2") (pintype "bidirectional"))
    )
    (net (code "154") (name "unconnected-(U3-NC-Pad1)") (class "Default")
      (node (ref "U3") (pin "1") (pinfunction "NC_1") (pintype "bidirectional"))
    )
    (net (code "155") (name "unconnected-(USB2-PadID)") (class "Default")
      (node (ref "USB2") (pin "ID") (pinfunction "ID_ID") (pintype "bidirectional"))
    )
    (net (code "156") (name "unconnected-(XB1-AD0{slash}DIO0-Pad20)") (class "Default")
      (node (ref "XB1") (pin "20") (pinfunction "AD0/DIO0_20") (pintype "bidirectional"))
    )
    (net (code "157") (name "unconnected-(XB1-AD1{slash}DIO1-Pad19)") (class "Default")
      (node (ref "XB1") (pin "19") (pinfunction "AD1/DIO1_19") (pintype "bidirectional"))
    )
    (net (code "158") (name "unconnected-(XB1-AD2{slash}DIO2-Pad18)") (class "Default")
      (node (ref "XB1") (pin "18") (pinfunction "AD2/DIO2_18") (pintype "bidirectional"))
    )
    (net (code "159") (name "unconnected-(XB1-ASSOC{slash}AD5{slash}DIO5-Pad15)") (class "Default")
      (node (ref "XB1") (pin "15") (pinfunction "ASSOC/AD5/DIO5_15") (pintype "bidirectional"))
    )
    (net (code "160") (name "unconnected-(XB1-CD{slash}DOUT_EN{slash}DO8-Pad4)") (class "Default")
      (node (ref "XB1") (pin "4") (pinfunction "CD/DOUT_EN/DO8_4") (pintype "output"))
    )
    (net (code "161") (name "unconnected-(XB1-COORD_SEL{slash}AD3{slash}DIO3-Pad17)") (class "Default")
      (node (ref "XB1") (pin "17") (pinfunction "COORD_SEL/AD3/DIO3_17") (pintype "bidirectional"))
    )
    (net (code "162") (name "unconnected-(XB1-ON{slash}~{SLEEP}-Pad13)") (class "Default")
      (node (ref "XB1") (pin "13") (pinfunction "ON/~{SLEEP}_13") (pintype "output"))
    )
    (net (code "163") (name "unconnected-(XB1-RF_TX{slash}AD4{slash}DIO4-Pad11)") (class "Default")
      (node (ref "XB1") (pin "11") (pinfunction "RF_TX/AD4/DIO4_11") (pintype "bidirectional"))
    )
    (net (code "164") (name "unconnected-(XB1-VREF-Pad14)") (class "Default")
      (node (ref "XB1") (pin "14") (pinfunction "VREF_14") (pintype "input"))
    )
    (net (code "165") (name "unconnected-(XB1-~{CTS}{slash}DIO7-Pad12)") (class "Default")
      (node (ref "XB1") (pin "12") (pinfunction "~{CTS}/DIO7_12") (pintype "bidirectional"))
    )
    (net (code "166") (name "unconnected-(XB1-~{DTR}{slash}SLEEP_RQ{slash}DI8-Pad9)") (class "Default")
      (node (ref "XB1") (pin "9") (pinfunction "~{DTR}/SLEEP_RQ/DI8_9") (pintype "bidirectional"))
    )
    (net (code "167") (name "unconnected-(XB1-~{RESET}-Pad5)") (class "Default")
      (node (ref "XB1") (pin "5") (pinfunction "~{RESET}_5") (pintype "input"))
    )
    (net (code "168") (name "unconnected-(XB1-~{RTS}{slash}AD6{slash}DIO6-Pad16)") (class "Default")
      (node (ref "XB1") (pin "16") (pinfunction "~{RTS}/AD6/DIO6_16") (pintype "bidirectional"))
    )
  )
)
